# FPGA.net
KiCad netlist of a schematic drawn in Altium Designer
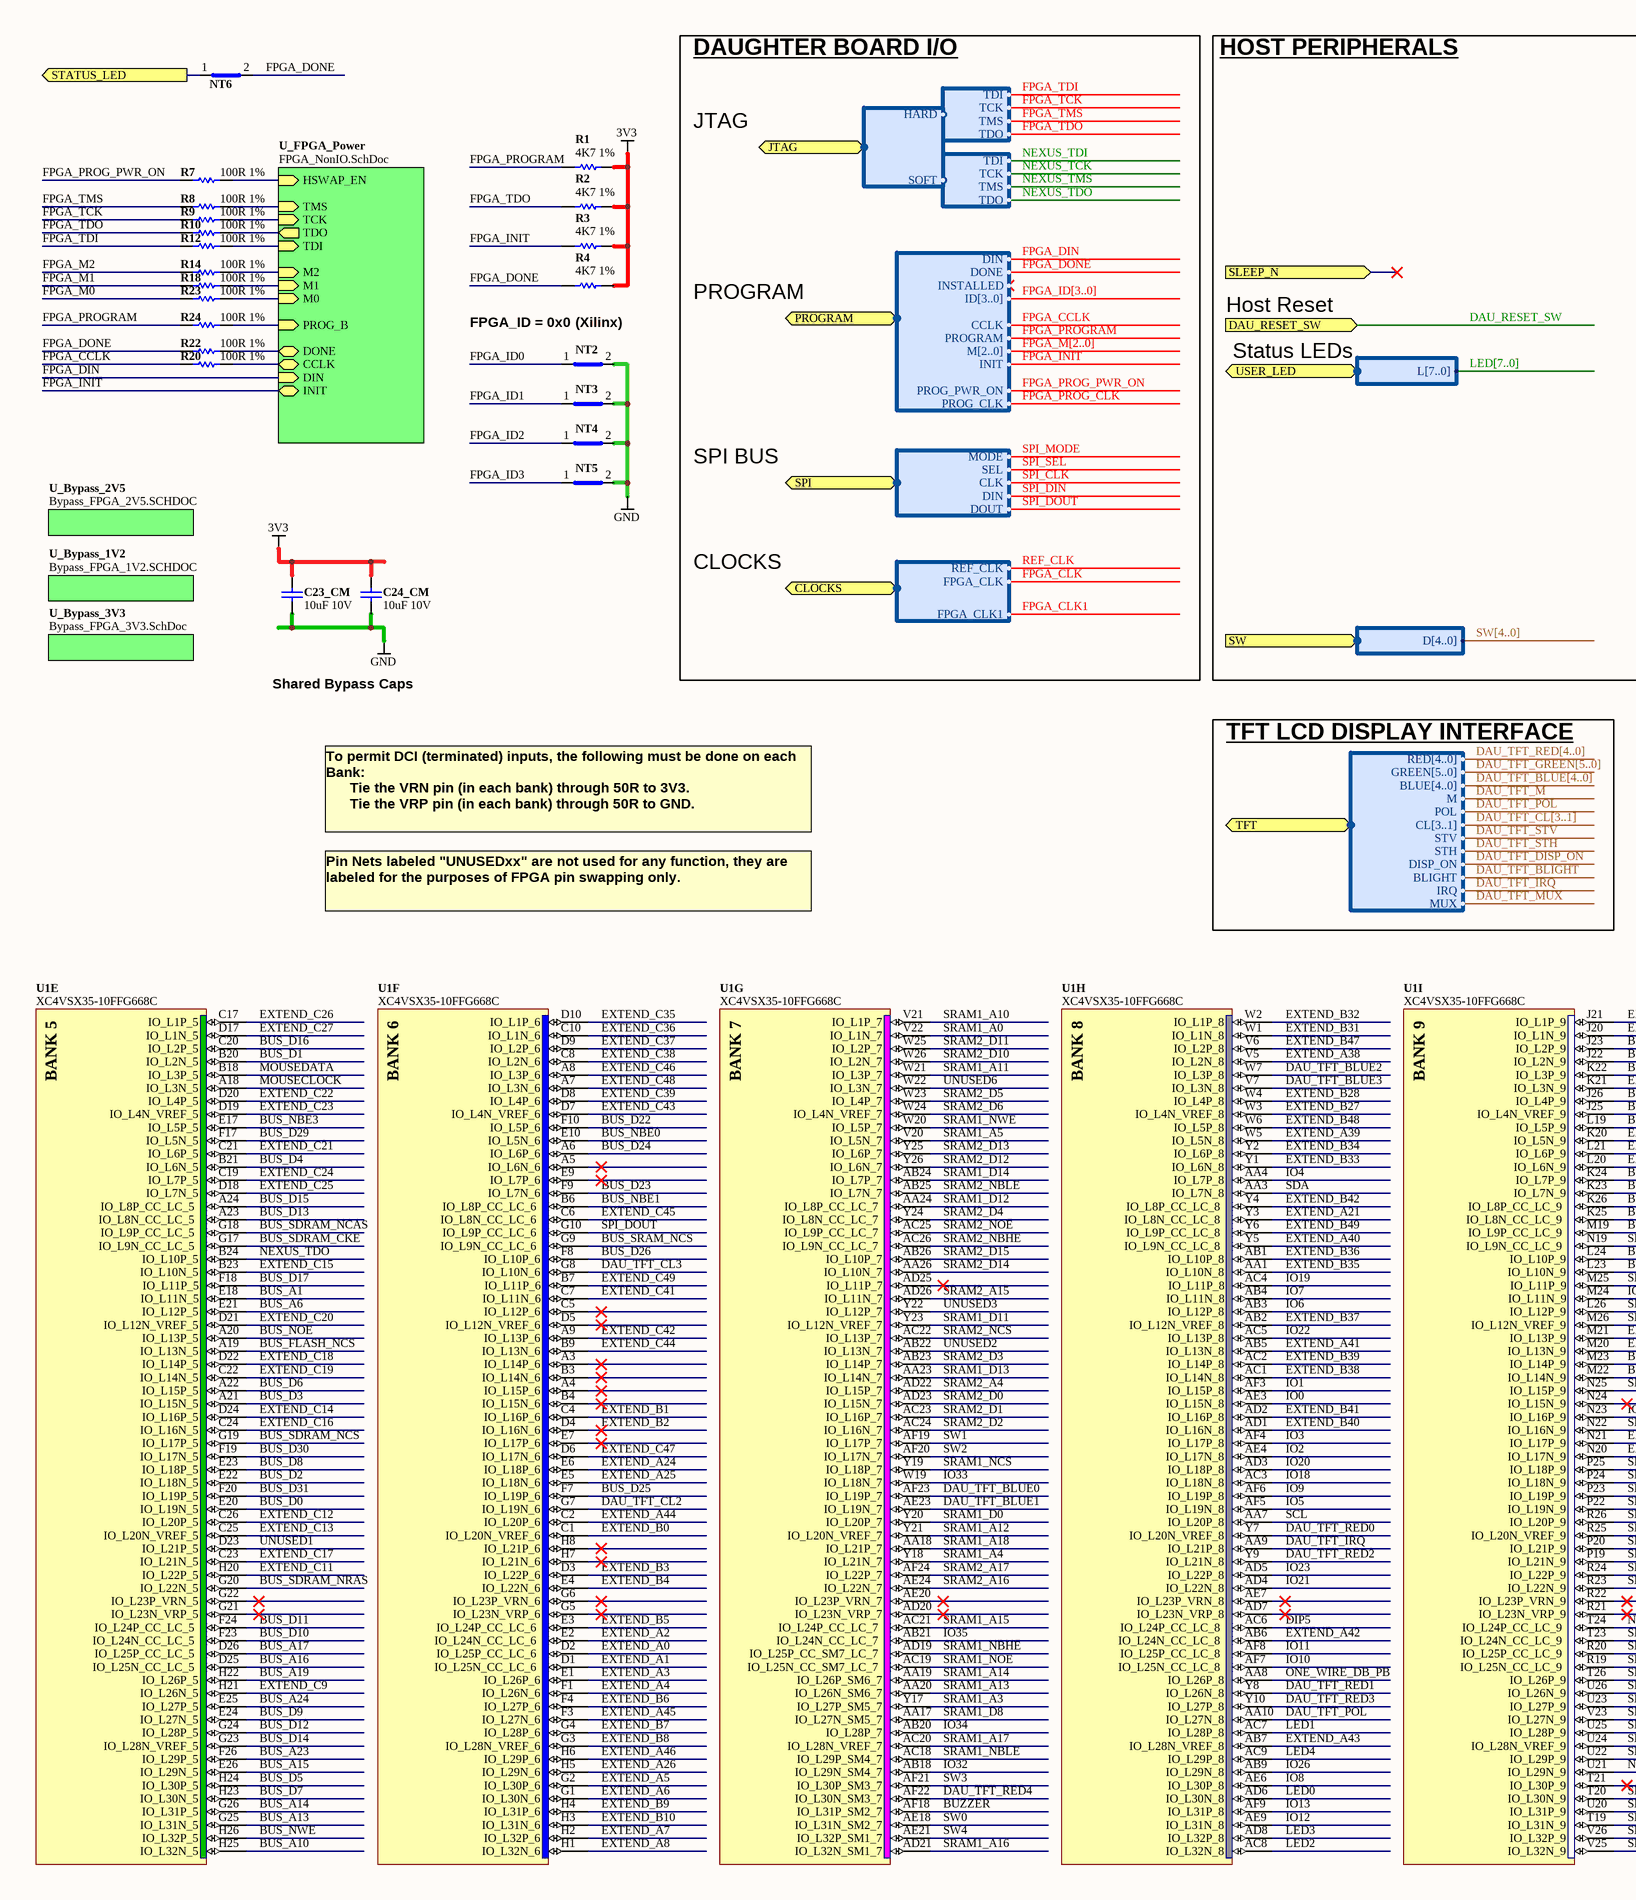
[diagram p0: FPGA.SCHDOC, left]
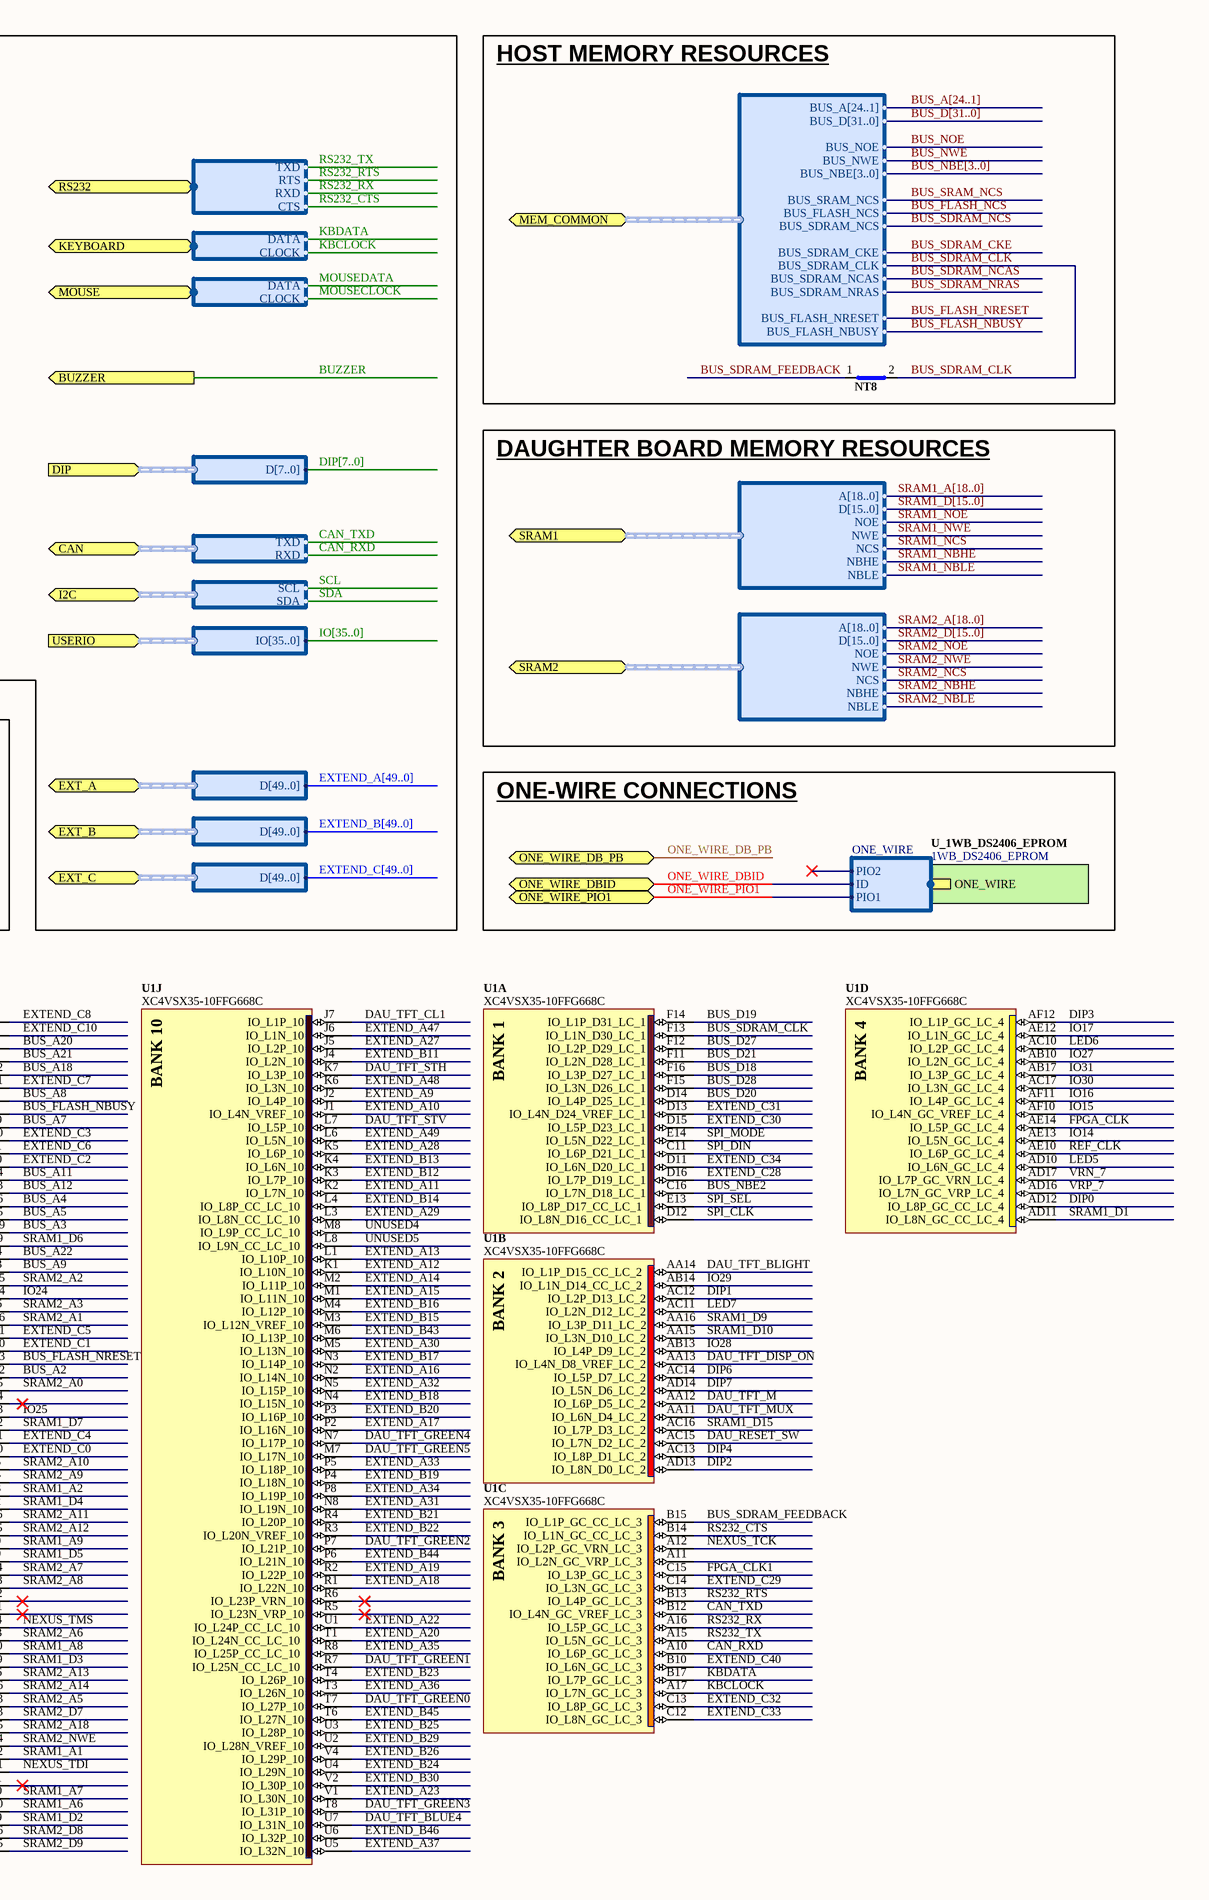
[diagram p1: FPGA.SCHDOC, right]

(export (version "E")
  (design (tool "Eeschema 10.0.6"))
  (components
    (comp (ref "C23_CM")
      (value "10uF 10V")
      (footprint "CAPC2012-STAR")
      (description "Capacitor, Ceramic, 10uF 10% 10V 0805 (2012) X5R")
      (fields (field (name "TOLERANCE") "10 %"))
      (libsource (lib "AltiumDesignLibrary") (part "CAP-NP"))
    )
    (comp (ref "C24_CM")
      (value "10uF 10V")
      (footprint "CAPC2012-STAR")
      (description "Capacitor, Ceramic, 10uF 10% 10V 0805 (2012) X5R")
      (fields (field (name "TOLERANCE") "10 %"))
      (libsource (lib "AltiumDesignLibrary") (part "CAP-NP"))
    )
    (comp (ref "NT2")
      (value "Net Tie SMT2")
      (footprint "NETTIE-SMT2-8X8")
      (description "Net-Tie, Surface Mount, 2 x 0.4mm x 0.2mm SMT Pads - For 0.2mm Track")
      (libsource (lib "AltiumDesignLibrary") (part "NETTIE-SMT2"))
    )
    (comp (ref "NT3")
      (value "Net Tie SMT2")
      (footprint "NETTIE-SMT2-8X8")
      (description "Net-Tie, Surface Mount, 2 x 0.4mm x 0.2mm SMT Pads - For 0.2mm Track")
      (libsource (lib "AltiumDesignLibrary") (part "NETTIE-SMT2"))
    )
    (comp (ref "NT4")
      (value "Net Tie SMT2")
      (footprint "NETTIE-SMT2-8X8")
      (description "Net-Tie, Surface Mount, 2 x 0.4mm x 0.2mm SMT Pads - For 0.2mm Track")
      (libsource (lib "AltiumDesignLibrary") (part "NETTIE-SMT2"))
    )
    (comp (ref "NT5")
      (value "Net Tie SMT2")
      (footprint "NETTIE-SMT2-8X8")
      (description "Net-Tie, Surface Mount, 2 x 0.4mm x 0.2mm SMT Pads - For 0.2mm Track")
      (libsource (lib "AltiumDesignLibrary") (part "NETTIE-SMT2"))
    )
    (comp (ref "NT6")
      (value "Net Tie SMT2")
      (footprint "NETTIE-SMT2-8X8")
      (description "Net-Tie, Surface Mount, 2 x 0.4mm x 0.2mm SMT Pads - For 0.2mm Track")
      (libsource (lib "AltiumDesignLibrary") (part "NETTIE-SMT2"))
    )
    (comp (ref "NT8")
      (value "Net Tie SMT2")
      (footprint "NETTIE-SMT2-8X8")
      (description "Net-Tie, Surface Mount, 2 x 0.4mm x 0.2mm SMT Pads - For 0.2mm Track")
      (libsource (lib "AltiumDesignLibrary") (part "NETTIE-SMT2"))
    )
    (comp (ref "R1")
      (value "4K7 1%")
      (footprint "RESC1005-STAR")
      (description "Resistor, 4K7 1% 0402 (1005)")
      (fields (field (name "TOLERANCE") "1 %"))
      (libsource (lib "AltiumDesignLibrary") (part "RES"))
    )
    (comp (ref "R2")
      (value "4K7 1%")
      (footprint "RESC1005-STAR")
      (description "Resistor, 4K7 1% 0402 (1005)")
      (fields (field (name "TOLERANCE") "1 %"))
      (libsource (lib "AltiumDesignLibrary") (part "RES"))
    )
    (comp (ref "R3")
      (value "4K7 1%")
      (footprint "RESC1005-STAR")
      (description "Resistor, 4K7 1% 0402 (1005)")
      (fields (field (name "TOLERANCE") "1 %"))
      (libsource (lib "AltiumDesignLibrary") (part "RES"))
    )
    (comp (ref "R4")
      (value "4K7 1%")
      (footprint "RESC1005-STAR")
      (description "Resistor, 4K7 1% 0402 (1005)")
      (fields (field (name "TOLERANCE") "1 %"))
      (libsource (lib "AltiumDesignLibrary") (part "RES"))
    )
    (comp (ref "R7")
      (value "100R 1%")
      (footprint "RESC1005-STAR")
      (description "Resistor, 100R 1% 0402 (1005)")
      (fields (field (name "TOLERANCE") "1 %"))
      (libsource (lib "AltiumDesignLibrary") (part "RES"))
    )
    (comp (ref "R8")
      (value "100R 1%")
      (footprint "RESC1005-STAR")
      (description "Resistor, 100R 1% 0402 (1005)")
      (fields (field (name "TOLERANCE") "1 %"))
      (libsource (lib "AltiumDesignLibrary") (part "RES"))
    )
    (comp (ref "R9")
      (value "100R 1%")
      (footprint "RESC1005-STAR")
      (description "Resistor, 100R 1% 0402 (1005)")
      (fields (field (name "TOLERANCE") "1 %"))
      (libsource (lib "AltiumDesignLibrary") (part "RES"))
    )
    (comp (ref "R10")
      (value "100R 1%")
      (footprint "RESC1005-STAR")
      (description "Resistor, 100R 1% 0402 (1005)")
      (fields (field (name "TOLERANCE") "1 %"))
      (libsource (lib "AltiumDesignLibrary") (part "RES"))
    )
    (comp (ref "R12")
      (value "100R 1%")
      (footprint "RESC1005-STAR")
      (description "Resistor, 100R 1% 0402 (1005)")
      (fields (field (name "TOLERANCE") "1 %"))
      (libsource (lib "AltiumDesignLibrary") (part "RES"))
    )
    (comp (ref "R14")
      (value "100R 1%")
      (footprint "RESC1005-STAR")
      (description "Resistor, 100R 1% 0402 (1005)")
      (fields (field (name "TOLERANCE") "1 %"))
      (libsource (lib "AltiumDesignLibrary") (part "RES"))
    )
    (comp (ref "R18")
      (value "100R 1%")
      (footprint "RESC1005-STAR")
      (description "Resistor, 100R 1% 0402 (1005)")
      (fields (field (name "TOLERANCE") "1 %"))
      (libsource (lib "AltiumDesignLibrary") (part "RES"))
    )
    (comp (ref "R20")
      (value "100R 1%")
      (footprint "RESC1005-STAR")
      (description "Resistor, 100R 1% 0402 (1005)")
      (fields (field (name "TOLERANCE") "1 %"))
      (libsource (lib "AltiumDesignLibrary") (part "RES"))
    )
    (comp (ref "R22")
      (value "100R 1%")
      (footprint "RESC1005-STAR")
      (description "Resistor, 100R 1% 0402 (1005)")
      (fields (field (name "TOLERANCE") "1 %"))
      (libsource (lib "AltiumDesignLibrary") (part "RES"))
    )
    (comp (ref "R23")
      (value "100R 1%")
      (footprint "RESC1005-STAR")
      (description "Resistor, 100R 1% 0402 (1005)")
      (fields (field (name "TOLERANCE") "1 %"))
      (libsource (lib "AltiumDesignLibrary") (part "RES"))
    )
    (comp (ref "R24")
      (value "100R 1%")
      (footprint "RESC1005-STAR")
      (description "Resistor, 100R 1% 0402 (1005)")
      (fields (field (name "TOLERANCE") "1 %"))
      (libsource (lib "AltiumDesignLibrary") (part "RES"))
    )
    (comp (ref "U1")
      (value "XC4VSX35-10FFG668C")
      (footprint "XC4VLX25-10FF668C")
      (description "FPGA, Xilinx Virtex-4, XC4VSX35")
      (libsource (lib "AltiumDesignLibrary") (part "XC4VSX35-10FFG668C"))
    )
  )
  (nets
    (net (code "20") (name "/BUS_A1") (class "Default")
      (node (ref "U1") (pin "E18") (pinfunction "IO_L11N_5_E18") (pintype "bidirectional"))
    )
    (net (code "21") (name "/BUS_A2") (class "Default")
      (node (ref "U1") (pin "M22") (pinfunction "IO_L14N_9_M22") (pintype "bidirectional"))
    )
    (net (code "22") (name "/BUS_A3") (class "Default")
      (node (ref "U1") (pin "M19") (pinfunction "IO_L9P_CC_LC_9_M19") (pintype "bidirectional"))
    )
    (net (code "23") (name "/BUS_A4") (class "Default")
      (node (ref "U1") (pin "K26") (pinfunction "IO_L8P_CC_LC_9_K26") (pintype "bidirectional"))
    )
    (net (code "24") (name "/BUS_A5") (class "Default")
      (node (ref "U1") (pin "K25") (pinfunction "IO_L8N_CC_LC_9_K25") (pintype "bidirectional"))
    )
    (net (code "25") (name "/BUS_A6") (class "Default")
      (node (ref "U1") (pin "E21") (pinfunction "IO_L12P_5_E21") (pintype "bidirectional"))
    )
    (net (code "26") (name "/BUS_A7") (class "Default")
      (node (ref "U1") (pin "L19") (pinfunction "IO_L5P_9_L19") (pintype "bidirectional"))
    )
    (net (code "27") (name "/BUS_A8") (class "Default")
      (node (ref "U1") (pin "J26") (pinfunction "IO_L4P_9_J26") (pintype "bidirectional"))
    )
    (net (code "28") (name "/BUS_A9") (class "Default")
      (node (ref "U1") (pin "L23") (pinfunction "IO_L10N_9_L23") (pintype "bidirectional"))
    )
    (net (code "29") (name "/BUS_A10") (class "Default")
      (node (ref "U1") (pin "H25") (pinfunction "IO_L32N_5_H25") (pintype "bidirectional"))
    )
    (net (code "30") (name "/BUS_A11") (class "Default")
      (node (ref "U1") (pin "K24") (pinfunction "IO_L7P_9_K24") (pintype "bidirectional"))
    )
    (net (code "31") (name "/BUS_A12") (class "Default")
      (node (ref "U1") (pin "K23") (pinfunction "IO_L7N_9_K23") (pintype "bidirectional"))
    )
    (net (code "32") (name "/BUS_A13") (class "Default")
      (node (ref "U1") (pin "G25") (pinfunction "IO_L31N_5_G25") (pintype "bidirectional"))
    )
    (net (code "33") (name "/BUS_A14") (class "Default")
      (node (ref "U1") (pin "G26") (pinfunction "IO_L31P_5_G26") (pintype "bidirectional"))
    )
    (net (code "34") (name "/BUS_A15") (class "Default")
      (node (ref "U1") (pin "E26") (pinfunction "IO_L29N_5_E26") (pintype "bidirectional"))
    )
    (net (code "35") (name "/BUS_A16") (class "Default")
      (node (ref "U1") (pin "D25") (pinfunction "IO_L25N_CC_LC_5_D25") (pintype "bidirectional"))
    )
    (net (code "36") (name "/BUS_A17") (class "Default")
      (node (ref "U1") (pin "D26") (pinfunction "IO_L25P_CC_LC_5_D26") (pintype "bidirectional"))
    )
    (net (code "37") (name "/BUS_A18") (class "Default")
      (node (ref "U1") (pin "K22") (pinfunction "IO_L3P_9_K22") (pintype "bidirectional"))
    )
    (net (code "38") (name "/BUS_A19") (class "Default")
      (node (ref "U1") (pin "H22") (pinfunction "IO_L26P_5_H22") (pintype "bidirectional"))
    )
    (net (code "39") (name "/BUS_A20") (class "Default")
      (node (ref "U1") (pin "J23") (pinfunction "IO_L2P_9_J23") (pintype "bidirectional"))
    )
    (net (code "40") (name "/BUS_A21") (class "Default")
      (node (ref "U1") (pin "J22") (pinfunction "IO_L2N_9_J22") (pintype "bidirectional"))
    )
    (net (code "41") (name "/BUS_A22") (class "Default")
      (node (ref "U1") (pin "L24") (pinfunction "IO_L10P_9_L24") (pintype "bidirectional"))
    )
    (net (code "42") (name "/BUS_A23") (class "Default")
      (node (ref "U1") (pin "F26") (pinfunction "IO_L29P_5_F26") (pintype "bidirectional"))
    )
    (net (code "43") (name "/BUS_A24") (class "Default")
      (node (ref "U1") (pin "E25") (pinfunction "IO_L27P_5_E25") (pintype "bidirectional"))
    )
    (net (code "44") (name "/BUS_D0") (class "Default")
      (node (ref "U1") (pin "E20") (pinfunction "IO_L19N_5_E20") (pintype "bidirectional"))
    )
    (net (code "45") (name "/BUS_D1") (class "Default")
      (node (ref "U1") (pin "B20") (pinfunction "IO_L2N_5_B20") (pintype "bidirectional"))
    )
    (net (code "46") (name "/BUS_D2") (class "Default")
      (node (ref "U1") (pin "E22") (pinfunction "IO_L18N_5_E22") (pintype "bidirectional"))
    )
    (net (code "47") (name "/BUS_D3") (class "Default")
      (node (ref "U1") (pin "A21") (pinfunction "IO_L15N_5_A21") (pintype "bidirectional"))
    )
    (net (code "48") (name "/BUS_D4") (class "Default")
      (node (ref "U1") (pin "B21") (pinfunction "IO_L6N_5_B21") (pintype "bidirectional"))
    )
    (net (code "49") (name "/BUS_D5") (class "Default")
      (node (ref "U1") (pin "H24") (pinfunction "IO_L30P_5_H24") (pintype "bidirectional"))
    )
    (net (code "50") (name "/BUS_D6") (class "Default")
      (node (ref "U1") (pin "A22") (pinfunction "IO_L15P_5_A22") (pintype "bidirectional"))
    )
    (net (code "51") (name "/BUS_D7") (class "Default")
      (node (ref "U1") (pin "H23") (pinfunction "IO_L30N_5_H23") (pintype "bidirectional"))
    )
    (net (code "52") (name "/BUS_D8") (class "Default")
      (node (ref "U1") (pin "E23") (pinfunction "IO_L18P_5_E23") (pintype "bidirectional"))
    )
    (net (code "53") (name "/BUS_D9") (class "Default")
      (node (ref "U1") (pin "E24") (pinfunction "IO_L27N_5_E24") (pintype "bidirectional"))
    )
    (net (code "54") (name "/BUS_D10") (class "Default")
      (node (ref "U1") (pin "F23") (pinfunction "IO_L24N_CC_LC_5_F23") (pintype "bidirectional"))
    )
    (net (code "55") (name "/BUS_D11") (class "Default")
      (node (ref "U1") (pin "F24") (pinfunction "IO_L24P_CC_LC_5_F24") (pintype "bidirectional"))
    )
    (net (code "56") (name "/BUS_D12") (class "Default")
      (node (ref "U1") (pin "G24") (pinfunction "IO_L28P_5_G24") (pintype "bidirectional"))
    )
    (net (code "57") (name "/BUS_D13") (class "Default")
      (node (ref "U1") (pin "A23") (pinfunction "IO_L8N_CC_LC_5_A23") (pintype "bidirectional"))
    )
    (net (code "58") (name "/BUS_D14") (class "Default")
      (node (ref "U1") (pin "G23") (pinfunction "IO_L28N_VREF_5_G23") (pintype "bidirectional"))
    )
    (net (code "59") (name "/BUS_D15") (class "Default")
      (node (ref "U1") (pin "A24") (pinfunction "IO_L8P_CC_LC_5_A24") (pintype "bidirectional"))
    )
    (net (code "60") (name "/BUS_D16") (class "Default")
      (node (ref "U1") (pin "C20") (pinfunction "IO_L2P_5_C20") (pintype "bidirectional"))
    )
    (net (code "61") (name "/BUS_D17") (class "Default")
      (node (ref "U1") (pin "F18") (pinfunction "IO_L11P_5_F18") (pintype "bidirectional"))
    )
    (net (code "62") (name "/BUS_D18") (class "Default")
      (node (ref "U1") (pin "F16") (pinfunction "IO_L3P_D27_LC_1_F16") (pintype "bidirectional"))
    )
    (net (code "63") (name "/BUS_D19") (class "Default")
      (node (ref "U1") (pin "F14") (pinfunction "IO_L1P_D31_LC_1_F14") (pintype "bidirectional"))
    )
    (net (code "64") (name "/BUS_D20") (class "Default")
      (node (ref "U1") (pin "D14") (pinfunction "IO_L4P_D25_LC_1_D14") (pintype "bidirectional"))
    )
    (net (code "65") (name "/BUS_D21") (class "Default")
      (node (ref "U1") (pin "F11") (pinfunction "IO_L2N_D28_LC_1_F11") (pintype "bidirectional"))
    )
    (net (code "66") (name "/BUS_D22") (class "Default")
      (node (ref "U1") (pin "F10") (pinfunction "IO_L5P_6_F10") (pintype "bidirectional"))
    )
    (net (code "67") (name "/BUS_D23") (class "Default")
      (node (ref "U1") (pin "F9") (pinfunction "IO_L7N_6_F9") (pintype "bidirectional"))
    )
    (net (code "68") (name "/BUS_D24") (class "Default")
      (node (ref "U1") (pin "A6") (pinfunction "IO_L6P_6_A6") (pintype "bidirectional"))
    )
    (net (code "69") (name "/BUS_D25") (class "Default")
      (node (ref "U1") (pin "F7") (pinfunction "IO_L19P_6_F7") (pintype "bidirectional"))
    )
    (net (code "70") (name "/BUS_D26") (class "Default")
      (node (ref "U1") (pin "F8") (pinfunction "IO_L10P_6_F8") (pintype "bidirectional"))
    )
    (net (code "71") (name "/BUS_D27") (class "Default")
      (node (ref "U1") (pin "F12") (pinfunction "IO_L2P_D29_LC_1_F12") (pintype "bidirectional"))
    )
    (net (code "72") (name "/BUS_D28") (class "Default")
      (node (ref "U1") (pin "F15") (pinfunction "IO_L3N_D26_LC_1_F15") (pintype "bidirectional"))
    )
    (net (code "73") (name "/BUS_D29") (class "Default")
      (node (ref "U1") (pin "F17") (pinfunction "IO_L5N_5_F17") (pintype "bidirectional"))
    )
    (net (code "74") (name "/BUS_D30") (class "Default")
      (node (ref "U1") (pin "F19") (pinfunction "IO_L17N_5_F19") (pintype "bidirectional"))
    )
    (net (code "75") (name "/BUS_D31") (class "Default")
      (node (ref "U1") (pin "F20") (pinfunction "IO_L19P_5_F20") (pintype "bidirectional"))
    )
    (net (code "77") (name "/BUS_FLASH_NBUSY") (class "Default")
      (node (ref "U1") (pin "J25") (pinfunction "IO_L4N_VREF_9_J25") (pintype "bidirectional"))
    )
    (net (code "78") (name "/BUS_FLASH_NCS") (class "Default")
      (node (ref "U1") (pin "A19") (pinfunction "IO_L13N_5_A19") (pintype "bidirectional"))
    )
    (net (code "79") (name "/BUS_FLASH_NRESET") (class "Default")
      (node (ref "U1") (pin "M23") (pinfunction "IO_L14P_9_M23") (pintype "bidirectional"))
    )
    (net (code "80") (name "/BUS_NBE0") (class "Default")
      (node (ref "U1") (pin "E10") (pinfunction "IO_L5N_6_E10") (pintype "bidirectional"))
    )
    (net (code "81") (name "/BUS_NBE1") (class "Default")
      (node (ref "U1") (pin "B6") (pinfunction "IO_L8P_CC_LC_6_B6") (pintype "bidirectional"))
    )
    (net (code "82") (name "/BUS_NBE2") (class "Default")
      (node (ref "U1") (pin "C16") (pinfunction "IO_L7N_D18_LC_1_C16") (pintype "bidirectional"))
    )
    (net (code "83") (name "/BUS_NBE3") (class "Default")
      (node (ref "U1") (pin "E17") (pinfunction "IO_L5P_5_E17") (pintype "bidirectional"))
    )
    (net (code "85") (name "/BUS_NOE") (class "Default")
      (node (ref "U1") (pin "A20") (pinfunction "IO_L13P_5_A20") (pintype "bidirectional"))
    )
    (net (code "86") (name "/BUS_NWE") (class "Default")
      (node (ref "U1") (pin "H26") (pinfunction "IO_L32P_5_H26") (pintype "bidirectional"))
    )
    (net (code "87") (name "/BUS_SDRAM_CKE") (class "Default")
      (node (ref "U1") (pin "G17") (pinfunction "IO_L9N_CC_LC_5_G17") (pintype "bidirectional"))
    )
    (net (code "88") (name "/BUS_SDRAM_CLK") (class "Default")
      (node (ref "NT8") (pin "2") (pinfunction "Net2_2") (pintype "passive"))
      (node (ref "U1") (pin "F13") (pinfunction "IO_L1N_D30_LC_1_F13") (pintype "bidirectional"))
    )
    (net (code "89") (name "/BUS_SDRAM_FEEDBACK") (class "Default")
      (node (ref "NT8") (pin "1") (pinfunction "Net1_1") (pintype "passive"))
      (node (ref "U1") (pin "B15") (pinfunction "IO_L1P_GC_CC_LC_3_B15") (pintype "bidirectional"))
    )
    (net (code "90") (name "/BUS_SDRAM_NCAS") (class "Default")
      (node (ref "U1") (pin "G18") (pinfunction "IO_L9P_CC_LC_5_G18") (pintype "bidirectional"))
    )
    (net (code "91") (name "/BUS_SDRAM_NCS") (class "Default")
      (node (ref "U1") (pin "G19") (pinfunction "IO_L17P_5_G19") (pintype "bidirectional"))
    )
    (net (code "92") (name "/BUS_SDRAM_NRAS") (class "Default")
      (node (ref "U1") (pin "G20") (pinfunction "IO_L22N_5_G20") (pintype "bidirectional"))
    )
    (net (code "93") (name "/BUS_SRAM_NCS") (class "Default")
      (node (ref "U1") (pin "G9") (pinfunction "IO_L9N_CC_LC_6_G9") (pintype "bidirectional"))
    )
    (net (code "94") (name "/BUZZER") (class "Default")
      (node (ref "U1") (pin "AF18") (pinfunction "IO_L31P_SM2_7_AF18") (pintype "bidirectional"))
    )
    (net (code "95") (name "/CAN_RXD") (class "Default")
      (node (ref "U1") (pin "A10") (pinfunction "IO_L6P_GC_LC_3_A10") (pintype "bidirectional"))
    )
    (net (code "96") (name "/CAN_TXD") (class "Default")
      (node (ref "U1") (pin "B12") (pinfunction "IO_L4N_GC_VREF_LC_3_B12") (pintype "bidirectional"))
    )
    (net (code "97") (name "/CCLK") (class "Default")
      (node (ref "R20") (pin "2") (pinfunction "2_2") (pintype "passive"))
    )
    (net (code "98") (name "/DAU_RESET_SW") (class "Default")
      (node (ref "U1") (pin "AC15") (pinfunction "IO_L7N_D2_LC_2_AC15") (pintype "bidirectional"))
    )
    (net (code "99") (name "/DAU_TFT_BLIGHT") (class "Default")
      (node (ref "U1") (pin "AA14") (pinfunction "IO_L1P_D15_CC_LC_2_AA14") (pintype "bidirectional"))
    )
    (net (code "100") (name "/DAU_TFT_BLUE0") (class "Default")
      (node (ref "U1") (pin "AF23") (pinfunction "IO_L19P_7_AF23") (pintype "bidirectional"))
    )
    (net (code "101") (name "/DAU_TFT_BLUE1") (class "Default")
      (node (ref "U1") (pin "AE23") (pinfunction "IO_L19N_7_AE23") (pintype "bidirectional"))
    )
    (net (code "102") (name "/DAU_TFT_BLUE2") (class "Default")
      (node (ref "U1") (pin "W7") (pinfunction "IO_L3P_8_W7") (pintype "bidirectional"))
    )
    (net (code "103") (name "/DAU_TFT_BLUE3") (class "Default")
      (node (ref "U1") (pin "V7") (pinfunction "IO_L3N_8_V7") (pintype "bidirectional"))
    )
    (net (code "104") (name "/DAU_TFT_BLUE4") (class "Default")
      (node (ref "U1") (pin "U7") (pinfunction "IO_L31N_10_U7") (pintype "bidirectional"))
    )
    (net (code "106") (name "/DAU_TFT_CL1") (class "Default")
      (node (ref "U1") (pin "J7") (pinfunction "IO_L1P_10_J7") (pintype "bidirectional"))
    )
    (net (code "107") (name "/DAU_TFT_CL2") (class "Default")
      (node (ref "U1") (pin "G7") (pinfunction "IO_L19N_6_G7") (pintype "bidirectional"))
    )
    (net (code "108") (name "/DAU_TFT_CL3") (class "Default")
      (node (ref "U1") (pin "G8") (pinfunction "IO_L10N_6_G8") (pintype "bidirectional"))
    )
    (net (code "110") (name "/DAU_TFT_DISP_ON") (class "Default")
      (node (ref "U1") (pin "AA13") (pinfunction "IO_L4N_D8_VREF_LC_2_AA13") (pintype "bidirectional"))
    )
    (net (code "111") (name "/DAU_TFT_GREEN0") (class "Default")
      (node (ref "U1") (pin "T7") (pinfunction "IO_L27P_10_T7") (pintype "bidirectional"))
    )
    (net (code "112") (name "/DAU_TFT_GREEN1") (class "Default")
      (node (ref "U1") (pin "R7") (pinfunction "IO_L25N_CC_LC_10_R7") (pintype "bidirectional"))
    )
    (net (code "113") (name "/DAU_TFT_GREEN2") (class "Default")
      (node (ref "U1") (pin "P7") (pinfunction "IO_L21P_10_P7") (pintype "bidirectional"))
    )
    (net (code "114") (name "/DAU_TFT_GREEN3") (class "Default")
      (node (ref "U1") (pin "T8") (pinfunction "IO_L31P_10_T8") (pintype "bidirectional"))
    )
    (net (code "115") (name "/DAU_TFT_GREEN4") (class "Default")
      (node (ref "U1") (pin "N7") (pinfunction "IO_L17P_10_N7") (pintype "bidirectional"))
    )
    (net (code "116") (name "/DAU_TFT_GREEN5") (class "Default")
      (node (ref "U1") (pin "M7") (pinfunction "IO_L17N_10_M7") (pintype "bidirectional"))
    )
    (net (code "117") (name "/DAU_TFT_IRQ") (class "Default")
      (node (ref "U1") (pin "AA9") (pinfunction "IO_L21P_8_AA9") (pintype "bidirectional"))
    )
    (net (code "118") (name "/DAU_TFT_M") (class "Default")
      (node (ref "U1") (pin "AA12") (pinfunction "IO_L6P_D5_LC_2_AA12") (pintype "bidirectional"))
    )
    (net (code "119") (name "/DAU_TFT_MUX") (class "Default")
      (node (ref "U1") (pin "AA11") (pinfunction "IO_L6N_D4_LC_2_AA11") (pintype "bidirectional"))
    )
    (net (code "120") (name "/DAU_TFT_POL") (class "Default")
      (node (ref "U1") (pin "AA10") (pinfunction "IO_L27N_8_AA10") (pintype "bidirectional"))
    )
    (net (code "121") (name "/DAU_TFT_RED0") (class "Default")
      (node (ref "U1") (pin "Y7") (pinfunction "IO_L20N_VREF_8_Y7") (pintype "bidirectional"))
    )
    (net (code "122") (name "/DAU_TFT_RED1") (class "Default")
      (node (ref "U1") (pin "Y8") (pinfunction "IO_L26N_8_Y8") (pintype "bidirectional"))
    )
    (net (code "123") (name "/DAU_TFT_RED2") (class "Default")
      (node (ref "U1") (pin "Y9") (pinfunction "IO_L21N_8_Y9") (pintype "bidirectional"))
    )
    (net (code "124") (name "/DAU_TFT_RED3") (class "Default")
      (node (ref "U1") (pin "Y10") (pinfunction "IO_L27P_8_Y10") (pintype "bidirectional"))
    )
    (net (code "125") (name "/DAU_TFT_RED4") (class "Default")
      (node (ref "U1") (pin "AF22") (pinfunction "IO_L30N_SM3_7_AF22") (pintype "bidirectional"))
    )
    (net (code "127") (name "/DAU_TFT_STH") (class "Default")
      (node (ref "U1") (pin "K7") (pinfunction "IO_L3P_10_K7") (pintype "bidirectional"))
    )
    (net (code "128") (name "/DAU_TFT_STV") (class "Default")
      (node (ref "U1") (pin "L7") (pinfunction "IO_L5P_10_L7") (pintype "bidirectional"))
    )
    (net (code "129") (name "/DIP0") (class "Default")
      (node (ref "U1") (pin "AD12") (pinfunction "IO_L8P_GC_CC_LC_4_AD12") (pintype "bidirectional"))
    )
    (net (code "130") (name "/DIP1") (class "Default")
      (node (ref "U1") (pin "AC12") (pinfunction "IO_L2P_D13_LC_2_AC12") (pintype "bidirectional"))
    )
    (net (code "131") (name "/DIP2") (class "Default")
      (node (ref "U1") (pin "AD13") (pinfunction "IO_L8N_D0_LC_2_AD13") (pintype "bidirectional"))
    )
    (net (code "132") (name "/DIP3") (class "Default")
      (node (ref "U1") (pin "AF12") (pinfunction "IO_L1P_GC_LC_4_AF12") (pintype "bidirectional"))
    )
    (net (code "133") (name "/DIP4") (class "Default")
      (node (ref "U1") (pin "AC13") (pinfunction "IO_L8P_D1_LC_2_AC13") (pintype "bidirectional"))
    )
    (net (code "134") (name "/DIP5") (class "Default")
      (node (ref "U1") (pin "AC6") (pinfunction "IO_L24P_CC_LC_8_AC6") (pintype "bidirectional"))
    )
    (net (code "135") (name "/DIP6") (class "Default")
      (node (ref "U1") (pin "AC14") (pinfunction "IO_L5P_D7_LC_2_AC14") (pintype "bidirectional"))
    )
    (net (code "136") (name "/DIP7") (class "Default")
      (node (ref "U1") (pin "AD14") (pinfunction "IO_L5N_D6_LC_2_AD14") (pintype "bidirectional"))
    )
    (net (code "138") (name "/DONE") (class "Default")
      (node (ref "R22") (pin "2") (pinfunction "2_2") (pintype "passive"))
    )
    (net (code "139") (name "/EXTEND_A0") (class "Default")
      (node (ref "U1") (pin "D2") (pinfunction "IO_L25P_CC_LC_6_D2") (pintype "bidirectional"))
    )
    (net (code "140") (name "/EXTEND_A1") (class "Default")
      (node (ref "U1") (pin "D1") (pinfunction "IO_L25N_CC_LC_6_D1") (pintype "bidirectional"))
    )
    (net (code "141") (name "/EXTEND_A2") (class "Default")
      (node (ref "U1") (pin "E2") (pinfunction "IO_L24N_CC_LC_6_E2") (pintype "bidirectional"))
    )
    (net (code "142") (name "/EXTEND_A3") (class "Default")
      (node (ref "U1") (pin "E1") (pinfunction "IO_L26P_6_E1") (pintype "bidirectional"))
    )
    (net (code "143") (name "/EXTEND_A4") (class "Default")
      (node (ref "U1") (pin "F1") (pinfunction "IO_L26N_6_F1") (pintype "bidirectional"))
    )
    (net (code "144") (name "/EXTEND_A5") (class "Default")
      (node (ref "U1") (pin "G2") (pinfunction "IO_L30P_6_G2") (pintype "bidirectional"))
    )
    (net (code "145") (name "/EXTEND_A6") (class "Default")
      (node (ref "U1") (pin "G1") (pinfunction "IO_L30N_6_G1") (pintype "bidirectional"))
    )
    (net (code "146") (name "/EXTEND_A7") (class "Default")
      (node (ref "U1") (pin "H2") (pinfunction "IO_L32P_6_H2") (pintype "bidirectional"))
    )
    (net (code "147") (name "/EXTEND_A8") (class "Default")
      (node (ref "U1") (pin "H1") (pinfunction "IO_L32N_6_H1") (pintype "bidirectional"))
    )
    (net (code "148") (name "/EXTEND_A9") (class "Default")
      (node (ref "U1") (pin "J2") (pinfunction "IO_L4P_10_J2") (pintype "bidirectional"))
    )
    (net (code "149") (name "/EXTEND_A10") (class "Default")
      (node (ref "U1") (pin "J1") (pinfunction "IO_L4N_VREF_10_J1") (pintype "bidirectional"))
    )
    (net (code "150") (name "/EXTEND_A11") (class "Default")
      (node (ref "U1") (pin "K2") (pinfunction "IO_L7N_10_K2") (pintype "bidirectional"))
    )
    (net (code "151") (name "/EXTEND_A12") (class "Default")
      (node (ref "U1") (pin "K1") (pinfunction "IO_L10N_10_K1") (pintype "bidirectional"))
    )
    (net (code "152") (name "/EXTEND_A13") (class "Default")
      (node (ref "U1") (pin "L1") (pinfunction "IO_L10P_10_L1") (pintype "bidirectional"))
    )
    (net (code "153") (name "/EXTEND_A14") (class "Default")
      (node (ref "U1") (pin "M2") (pinfunction "IO_L11P_10_M2") (pintype "bidirectional"))
    )
    (net (code "154") (name "/EXTEND_A15") (class "Default")
      (node (ref "U1") (pin "M1") (pinfunction "IO_L11N_10_M1") (pintype "bidirectional"))
    )
    (net (code "155") (name "/EXTEND_A16") (class "Default")
      (node (ref "U1") (pin "N2") (pinfunction "IO_L14N_10_N2") (pintype "bidirectional"))
    )
    (net (code "156") (name "/EXTEND_A17") (class "Default")
      (node (ref "U1") (pin "P2") (pinfunction "IO_L16N_10_P2") (pintype "bidirectional"))
    )
    (net (code "157") (name "/EXTEND_A18") (class "Default")
      (node (ref "U1") (pin "R1") (pinfunction "IO_L22N_10_R1") (pintype "bidirectional"))
    )
    (net (code "158") (name "/EXTEND_A19") (class "Default")
      (node (ref "U1") (pin "R2") (pinfunction "IO_L22P_10_R2") (pintype "bidirectional"))
    )
    (net (code "159") (name "/EXTEND_A20") (class "Default")
      (node (ref "U1") (pin "T1") (pinfunction "IO_L24N_CC_LC_10_T1") (pintype "bidirectional"))
    )
    (net (code "160") (name "/EXTEND_A21") (class "Default")
      (node (ref "U1") (pin "Y3") (pinfunction "IO_L8N_CC_LC_8_Y3") (pintype "bidirectional"))
    )
    (net (code "161") (name "/EXTEND_A22") (class "Default")
      (node (ref "U1") (pin "U1") (pinfunction "IO_L24P_CC_LC_10_U1") (pintype "bidirectional"))
    )
    (net (code "162") (name "/EXTEND_A23") (class "Default")
      (node (ref "U1") (pin "V1") (pinfunction "IO_L30N_10_V1") (pintype "bidirectional"))
    )
    (net (code "163") (name "/EXTEND_A24") (class "Default")
      (node (ref "U1") (pin "E6") (pinfunction "IO_L18P_6_E6") (pintype "bidirectional"))
    )
    (net (code "164") (name "/EXTEND_A25") (class "Default")
      (node (ref "U1") (pin "E5") (pinfunction "IO_L18N_6_E5") (pintype "bidirectional"))
    )
    (net (code "165") (name "/EXTEND_A26") (class "Default")
      (node (ref "U1") (pin "H5") (pinfunction "IO_L29N_6_H5") (pintype "bidirectional"))
    )
    (net (code "166") (name "/EXTEND_A27") (class "Default")
      (node (ref "U1") (pin "J5") (pinfunction "IO_L2P_10_J5") (pintype "bidirectional"))
    )
    (net (code "167") (name "/EXTEND_A28") (class "Default")
      (node (ref "U1") (pin "K5") (pinfunction "IO_L6P_10_K5") (pintype "bidirectional"))
    )
    (net (code "168") (name "/EXTEND_A29") (class "Default")
      (node (ref "U1") (pin "L3") (pinfunction "IO_L8N_CC_LC_10_L3") (pintype "bidirectional"))
    )
    (net (code "169") (name "/EXTEND_A30") (class "Default")
      (node (ref "U1") (pin "M5") (pinfunction "IO_L13N_10_M5") (pintype "bidirectional"))
    )
    (net (code "170") (name "/EXTEND_A31") (class "Default")
      (node (ref "U1") (pin "N8") (pinfunction "IO_L19N_10_N8") (pintype "bidirectional"))
    )
    (net (code "171") (name "/EXTEND_A32") (class "Default")
      (node (ref "U1") (pin "N5") (pinfunction "IO_L15P_10_N5") (pintype "bidirectional"))
    )
    (net (code "172") (name "/EXTEND_A33") (class "Default")
      (node (ref "U1") (pin "P5") (pinfunction "IO_L18P_10_P5") (pintype "bidirectional"))
    )
    (net (code "173") (name "/EXTEND_A34") (class "Default")
      (node (ref "U1") (pin "P8") (pinfunction "IO_L19P_10_P8") (pintype "bidirectional"))
    )
    (net (code "174") (name "/EXTEND_A35") (class "Default")
      (node (ref "U1") (pin "R8") (pinfunction "IO_L25P_CC_LC_10_R8") (pintype "bidirectional"))
    )
    (net (code "175") (name "/EXTEND_A36") (class "Default")
      (node (ref "U1") (pin "T3") (pinfunction "IO_L26N_10_T3") (pintype "bidirectional"))
    )
    (net (code "176") (name "/EXTEND_A37") (class "Default")
      (node (ref "U1") (pin "U5") (pinfunction "IO_L32N_10_U5") (pintype "bidirectional"))
    )
    (net (code "177") (name "/EXTEND_A38") (class "Default")
      (node (ref "U1") (pin "V5") (pinfunction "IO_L2N_8_V5") (pintype "bidirectional"))
    )
    (net (code "178") (name "/EXTEND_A39") (class "Default")
      (node (ref "U1") (pin "W5") (pinfunction "IO_L5N_8_W5") (pintype "bidirectional"))
    )
    (net (code "179") (name "/EXTEND_A40") (class "Default")
      (node (ref "U1") (pin "Y5") (pinfunction "IO_L9N_CC_LC_8_Y5") (pintype "bidirectional"))
    )
    (net (code "180") (name "/EXTEND_A41") (class "Default")
      (node (ref "U1") (pin "AB5") (pinfunction "IO_L13N_8_AB5") (pintype "bidirectional"))
    )
    (net (code "181") (name "/EXTEND_A42") (class "Default")
      (node (ref "U1") (pin "AB6") (pinfunction "IO_L24N_CC_LC_8_AB6") (pintype "bidirectional"))
    )
    (net (code "182") (name "/EXTEND_A43") (class "Default")
      (node (ref "U1") (pin "AB7") (pinfunction "IO_L28N_VREF_8_AB7") (pintype "bidirectional"))
    )
    (net (code "183") (name "/EXTEND_A44") (class "Default")
      (node (ref "U1") (pin "C2") (pinfunction "IO_L20P_6_C2") (pintype "bidirectional"))
    )
    (net (code "184") (name "/EXTEND_A45") (class "Default")
      (node (ref "U1") (pin "F3") (pinfunction "IO_L27N_6_F3") (pintype "bidirectional"))
    )
    (net (code "185") (name "/EXTEND_A46") (class "Default")
      (node (ref "U1") (pin "H6") (pinfunction "IO_L29P_6_H6") (pintype "bidirectional"))
    )
    (net (code "186") (name "/EXTEND_A47") (class "Default")
      (node (ref "U1") (pin "J6") (pinfunction "IO_L1N_10_J6") (pintype "bidirectional"))
    )
    (net (code "187") (name "/EXTEND_A48") (class "Default")
      (node (ref "U1") (pin "K6") (pinfunction "IO_L3N_10_K6") (pintype "bidirectional"))
    )
    (net (code "188") (name "/EXTEND_A49") (class "Default")
      (node (ref "U1") (pin "L6") (pinfunction "IO_L5N_10_L6") (pintype "bidirectional"))
    )
    (net (code "189") (name "/EXTEND_B0") (class "Default")
      (node (ref "U1") (pin "C1") (pinfunction "IO_L20N_VREF_6_C1") (pintype "bidirectional"))
    )
    (net (code "190") (name "/EXTEND_B1") (class "Default")
      (node (ref "U1") (pin "C4") (pinfunction "IO_L16P_6_C4") (pintype "bidirectional"))
    )
    (net (code "191") (name "/EXTEND_B2") (class "Default")
      (node (ref "U1") (pin "D4") (pinfunction "IO_L16N_6_D4") (pintype "bidirectional"))
    )
    (net (code "192") (name "/EXTEND_B3") (class "Default")
      (node (ref "U1") (pin "D3") (pinfunction "IO_L22P_6_D3") (pintype "bidirectional"))
    )
    (net (code "193") (name "/EXTEND_B4") (class "Default")
      (node (ref "U1") (pin "E4") (pinfunction "IO_L22N_6_E4") (pintype "bidirectional"))
    )
    (net (code "194") (name "/EXTEND_B5") (class "Default")
      (node (ref "U1") (pin "E3") (pinfunction "IO_L24P_CC_LC_6_E3") (pintype "bidirectional"))
    )
    (net (code "195") (name "/EXTEND_B6") (class "Default")
      (node (ref "U1") (pin "F4") (pinfunction "IO_L27P_6_F4") (pintype "bidirectional"))
    )
    (net (code "196") (name "/EXTEND_B7") (class "Default")
      (node (ref "U1") (pin "G4") (pinfunction "IO_L28P_6_G4") (pintype "bidirectional"))
    )
    (net (code "197") (name "/EXTEND_B8") (class "Default")
      (node (ref "U1") (pin "G3") (pinfunction "IO_L28N_VREF_6_G3") (pintype "bidirectional"))
    )
    (net (code "198") (name "/EXTEND_B9") (class "Default")
      (node (ref "U1") (pin "H4") (pinfunction "IO_L31P_6_H4") (pintype "bidirectional"))
    )
    (net (code "199") (name "/EXTEND_B10") (class "Default")
      (node (ref "U1") (pin "H3") (pinfunction "IO_L31N_6_H3") (pintype "bidirectional"))
    )
    (net (code "200") (name "/EXTEND_B11") (class "Default")
      (node (ref "U1") (pin "J4") (pinfunction "IO_L2N_10_J4") (pintype "bidirectional"))
    )
    (net (code "201") (name "/EXTEND_B12") (class "Default")
      (node (ref "U1") (pin "K3") (pinfunction "IO_L7P_10_K3") (pintype "bidirectional"))
    )
    (net (code "202") (name "/EXTEND_B13") (class "Default")
      (node (ref "U1") (pin "K4") (pinfunction "IO_L6N_10_K4") (pintype "bidirectional"))
    )
    (net (code "203") (name "/EXTEND_B14") (class "Default")
      (node (ref "U1") (pin "L4") (pinfunction "IO_L8P_CC_LC_10_L4") (pintype "bidirectional"))
    )
    (net (code "204") (name "/EXTEND_B15") (class "Default")
      (node (ref "U1") (pin "M3") (pinfunction "IO_L12N_VREF_10_M3") (pintype "bidirectional"))
    )
    (net (code "205") (name "/EXTEND_B16") (class "Default")
      (node (ref "U1") (pin "M4") (pinfunction "IO_L12P_10_M4") (pintype "bidirectional"))
    )
    (net (code "206") (name "/EXTEND_B17") (class "Default")
      (node (ref "U1") (pin "N3") (pinfunction "IO_L14P_10_N3") (pintype "bidirectional"))
    )
    (net (code "207") (name "/EXTEND_B18") (class "Default")
      (node (ref "U1") (pin "N4") (pinfunction "IO_L15N_10_N4") (pintype "bidirectional"))
    )
    (net (code "208") (name "/EXTEND_B19") (class "Default")
      (node (ref "U1") (pin "P4") (pinfunction "IO_L18N_10_P4") (pintype "bidirectional"))
    )
    (net (code "209") (name "/EXTEND_B20") (class "Default")
      (node (ref "U1") (pin "P3") (pinfunction "IO_L16P_10_P3") (pintype "bidirectional"))
    )
    (net (code "210") (name "/EXTEND_B21") (class "Default")
      (node (ref "U1") (pin "R4") (pinfunction "IO_L20P_10_R4") (pintype "bidirectional"))
    )
    (net (code "211") (name "/EXTEND_B22") (class "Default")
      (node (ref "U1") (pin "R3") (pinfunction "IO_L20N_VREF_10_R3") (pintype "bidirectional"))
    )
    (net (code "212") (name "/EXTEND_B23") (class "Default")
      (node (ref "U1") (pin "T4") (pinfunction "IO_L26P_10_T4") (pintype "bidirectional"))
    )
    (net (code "213") (name "/EXTEND_B24") (class "Default")
      (node (ref "U1") (pin "U4") (pinfunction "IO_L29N_10_U4") (pintype "bidirectional"))
    )
    (net (code "214") (name "/EXTEND_B25") (class "Default")
      (node (ref "U1") (pin "U3") (pinfunction "IO_L28P_10_U3") (pintype "bidirectional"))
    )
    (net (code "215") (name "/EXTEND_B26") (class "Default")
      (node (ref "U1") (pin "V4") (pinfunction "IO_L29P_10_V4") (pintype "bidirectional"))
    )
    (net (code "216") (name "/EXTEND_B27") (class "Default")
      (node (ref "U1") (pin "W3") (pinfunction "IO_L4N_VREF_8_W3") (pintype "bidirectional"))
    )
    (net (code "217") (name "/EXTEND_B28") (class "Default")
      (node (ref "U1") (pin "W4") (pinfunction "IO_L4P_8_W4") (pintype "bidirectional"))
    )
    (net (code "218") (name "/EXTEND_B29") (class "Default")
      (node (ref "U1") (pin "U2") (pinfunction "IO_L28N_VREF_10_U2") (pintype "bidirectional"))
    )
    (net (code "219") (name "/EXTEND_B30") (class "Default")
      (node (ref "U1") (pin "V2") (pinfunction "IO_L30P_10_V2") (pintype "bidirectional"))
    )
    (net (code "220") (name "/EXTEND_B31") (class "Default")
      (node (ref "U1") (pin "W1") (pinfunction "IO_L1N_8_W1") (pintype "bidirectional"))
    )
    (net (code "221") (name "/EXTEND_B32") (class "Default")
      (node (ref "U1") (pin "W2") (pinfunction "IO_L1P_8_W2") (pintype "bidirectional"))
    )
    (net (code "222") (name "/EXTEND_B33") (class "Default")
      (node (ref "U1") (pin "Y1") (pinfunction "IO_L6N_8_Y1") (pintype "bidirectional"))
    )
    (net (code "223") (name "/EXTEND_B34") (class "Default")
      (node (ref "U1") (pin "Y2") (pinfunction "IO_L6P_8_Y2") (pintype "bidirectional"))
    )
    (net (code "224") (name "/EXTEND_B35") (class "Default")
      (node (ref "U1") (pin "AA1") (pinfunction "IO_L10N_8_AA1") (pintype "bidirectional"))
    )
    (net (code "225") (name "/EXTEND_B36") (class "Default")
      (node (ref "U1") (pin "AB1") (pinfunction "IO_L10P_8_AB1") (pintype "bidirectional"))
    )
    (net (code "226") (name "/EXTEND_B37") (class "Default")
      (node (ref "U1") (pin "AB2") (pinfunction "IO_L12N_VREF_8_AB2") (pintype "bidirectional"))
    )
    (net (code "227") (name "/EXTEND_B38") (class "Default")
      (node (ref "U1") (pin "AC1") (pinfunction "IO_L14N_8_AC1") (pintype "bidirectional"))
    )
    (net (code "228") (name "/EXTEND_B39") (class "Default")
      (node (ref "U1") (pin "AC2") (pinfunction "IO_L14P_8_AC2") (pintype "bidirectional"))
    )
    (net (code "229") (name "/EXTEND_B40") (class "Default")
      (node (ref "U1") (pin "AD1") (pinfunction "IO_L16N_8_AD1") (pintype "bidirectional"))
    )
    (net (code "230") (name "/EXTEND_B41") (class "Default")
      (node (ref "U1") (pin "AD2") (pinfunction "IO_L16P_8_AD2") (pintype "bidirectional"))
    )
    (net (code "231") (name "/EXTEND_B42") (class "Default")
      (node (ref "U1") (pin "Y4") (pinfunction "IO_L8P_CC_LC_8_Y4") (pintype "bidirectional"))
    )
    (net (code "232") (name "/EXTEND_B43") (class "Default")
      (node (ref "U1") (pin "M6") (pinfunction "IO_L13P_10_M6") (pintype "bidirectional"))
    )
    (net (code "233") (name "/EXTEND_B44") (class "Default")
      (node (ref "U1") (pin "P6") (pinfunction "IO_L21N_10_P6") (pintype "bidirectional"))
    )
    (net (code "234") (name "/EXTEND_B45") (class "Default")
      (node (ref "U1") (pin "T6") (pinfunction "IO_L27N_10_T6") (pintype "bidirectional"))
    )
    (net (code "235") (name "/EXTEND_B46") (class "Default")
      (node (ref "U1") (pin "U6") (pinfunction "IO_L32P_10_U6") (pintype "bidirectional"))
    )
    (net (code "236") (name "/EXTEND_B47") (class "Default")
      (node (ref "U1") (pin "V6") (pinfunction "IO_L2P_8_V6") (pintype "bidirectional"))
    )
    (net (code "237") (name "/EXTEND_B48") (class "Default")
      (node (ref "U1") (pin "W6") (pinfunction "IO_L5P_8_W6") (pintype "bidirectional"))
    )
    (net (code "238") (name "/EXTEND_B49") (class "Default")
      (node (ref "U1") (pin "Y6") (pinfunction "IO_L9P_CC_LC_8_Y6") (pintype "bidirectional"))
    )
    (net (code "239") (name "/EXTEND_C0") (class "Default")
      (node (ref "U1") (pin "N20") (pinfunction "IO_L17N_9_N20") (pintype "bidirectional"))
    )
    (net (code "240") (name "/EXTEND_C1") (class "Default")
      (node (ref "U1") (pin "M20") (pinfunction "IO_L13N_9_M20") (pintype "bidirectional"))
    )
    (net (code "241") (name "/EXTEND_C2") (class "Default")
      (node (ref "U1") (pin "L20") (pinfunction "IO_L6N_9_L20") (pintype "bidirectional"))
    )
    (net (code "242") (name "/EXTEND_C3") (class "Default")
      (node (ref "U1") (pin "K20") (pinfunction "IO_L5N_9_K20") (pintype "bidirectional"))
    )
    (net (code "243") (name "/EXTEND_C4") (class "Default")
      (node (ref "U1") (pin "N21") (pinfunction "IO_L17P_9_N21") (pintype "bidirectional"))
    )
    (net (code "244") (name "/EXTEND_C5") (class "Default")
      (node (ref "U1") (pin "M21") (pinfunction "IO_L13P_9_M21") (pintype "bidirectional"))
    )
    (net (code "245") (name "/EXTEND_C6") (class "Default")
      (node (ref "U1") (pin "L21") (pinfunction "IO_L6P_9_L21") (pintype "bidirectional"))
    )
    (net (code "246") (name "/EXTEND_C7") (class "Default")
      (node (ref "U1") (pin "K21") (pinfunction "IO_L3N_9_K21") (pintype "bidirectional"))
    )
    (net (code "247") (name "/EXTEND_C8") (class "Default")
      (node (ref "U1") (pin "J21") (pinfunction "IO_L1P_9_J21") (pintype "bidirectional"))
    )
    (net (code "248") (name "/EXTEND_C9") (class "Default")
      (node (ref "U1") (pin "H21") (pinfunction "IO_L26N_5_H21") (pintype "bidirectional"))
    )
    (net (code "249") (name "/EXTEND_C10") (class "Default")
      (node (ref "U1") (pin "J20") (pinfunction "IO_L1N_9_J20") (pintype "bidirectional"))
    )
    (net (code "250") (name "/EXTEND_C11") (class "Default")
      (node (ref "U1") (pin "H20") (pinfunction "IO_L22P_5_H20") (pintype "bidirectional"))
    )
    (net (code "251") (name "/EXTEND_C12") (class "Default")
      (node (ref "U1") (pin "C26") (pinfunction "IO_L20P_5_C26") (pintype "bidirectional"))
    )
    (net (code "252") (name "/EXTEND_C13") (class "Default")
      (node (ref "U1") (pin "C25") (pinfunction "IO_L20N_VREF_5_C25") (pintype "bidirectional"))
    )
    (net (code "253") (name "/EXTEND_C14") (class "Default")
      (node (ref "U1") (pin "D24") (pinfunction "IO_L16P_5_D24") (pintype "bidirectional"))
    )
    (net (code "254") (name "/EXTEND_C15") (class "Default")
      (node (ref "U1") (pin "B23") (pinfunction "IO_L10N_5_B23") (pintype "bidirectional"))
    )
    (net (code "255") (name "/EXTEND_C16") (class "Default")
      (node (ref "U1") (pin "C24") (pinfunction "IO_L16N_5_C24") (pintype "bidirectional"))
    )
    (net (code "256") (name "/EXTEND_C17") (class "Default")
      (node (ref "U1") (pin "C23") (pinfunction "IO_L21N_5_C23") (pintype "bidirectional"))
    )
    (net (code "257") (name "/EXTEND_C18") (class "Default")
      (node (ref "U1") (pin "D22") (pinfunction "IO_L14P_5_D22") (pintype "bidirectional"))
    )
    (net (code "258") (name "/EXTEND_C19") (class "Default")
      (node (ref "U1") (pin "C22") (pinfunction "IO_L14N_5_C22") (pintype "bidirectional"))
    )
    (net (code "259") (name "/EXTEND_C20") (class "Default")
      (node (ref "U1") (pin "D21") (pinfunction "IO_L12N_VREF_5_D21") (pintype "bidirectional"))
    )
    (net (code "260") (name "/EXTEND_C21") (class "Default")
      (node (ref "U1") (pin "C21") (pinfunction "IO_L6P_5_C21") (pintype "bidirectional"))
    )
    (net (code "261") (name "/EXTEND_C22") (class "Default")
      (node (ref "U1") (pin "D20") (pinfunction "IO_L4P_5_D20") (pintype "bidirectional"))
    )
    (net (code "262") (name "/EXTEND_C23") (class "Default")
      (node (ref "U1") (pin "D19") (pinfunction "IO_L4N_VREF_5_D19") (pintype "bidirectional"))
    )
    (net (code "263") (name "/EXTEND_C24") (class "Default")
      (node (ref "U1") (pin "C19") (pinfunction "IO_L7P_5_C19") (pintype "bidirectional"))
    )
    (net (code "264") (name "/EXTEND_C25") (class "Default")
      (node (ref "U1") (pin "D18") (pinfunction "IO_L7N_5_D18") (pintype "bidirectional"))
    )
    (net (code "265") (name "/EXTEND_C26") (class "Default")
      (node (ref "U1") (pin "C17") (pinfunction "IO_L1P_5_C17") (pintype "bidirectional"))
    )
    (net (code "266") (name "/EXTEND_C27") (class "Default")
      (node (ref "U1") (pin "D17") (pinfunction "IO_L1N_5_D17") (pintype "bidirectional"))
    )
    (net (code "267") (name "/EXTEND_C28") (class "Default")
      (node (ref "U1") (pin "D16") (pinfunction "IO_L7P_D19_LC_1_D16") (pintype "bidirectional"))
    )
    (net (code "268") (name "/EXTEND_C29") (class "Default")
      (node (ref "U1") (pin "C14") (pinfunction "IO_L3N_GC_LC_3_C14") (pintype "bidirectional"))
    )
    (net (code "269") (name "/EXTEND_C30") (class "Default")
      (node (ref "U1") (pin "D15") (pinfunction "IO_L5P_D23_LC_1_D15") (pintype "bidirectional"))
    )
    (net (code "270") (name "/EXTEND_C31") (class "Default")
      (node (ref "U1") (pin "D13") (pinfunction "IO_L4N_D24_VREF_LC_1_D13") (pintype "bidirectional"))
    )
    (net (code "271") (name "/EXTEND_C32") (class "Default")
      (node (ref "U1") (pin "C13") (pinfunction "IO_L8P_GC_LC_3_C13") (pintype "bidirectional"))
    )
    (net (code "272") (name "/EXTEND_C33") (class "Default")
      (node (ref "U1") (pin "C12") (pinfunction "IO_L8N_GC_LC_3_C12") (pintype "bidirectional"))
    )
    (net (code "273") (name "/EXTEND_C34") (class "Default")
      (node (ref "U1") (pin "D11") (pinfunction "IO_L6N_D20_LC_1_D11") (pintype "bidirectional"))
    )
    (net (code "274") (name "/EXTEND_C35") (class "Default")
      (node (ref "U1") (pin "D10") (pinfunction "IO_L1P_6_D10") (pintype "bidirectional"))
    )
    (net (code "275") (name "/EXTEND_C36") (class "Default")
      (node (ref "U1") (pin "C10") (pinfunction "IO_L1N_6_C10") (pintype "bidirectional"))
    )
    (net (code "276") (name "/EXTEND_C37") (class "Default")
      (node (ref "U1") (pin "D9") (pinfunction "IO_L2P_6_D9") (pintype "bidirectional"))
    )
    (net (code "277") (name "/EXTEND_C38") (class "Default")
      (node (ref "U1") (pin "C8") (pinfunction "IO_L2N_6_C8") (pintype "bidirectional"))
    )
    (net (code "278") (name "/EXTEND_C39") (class "Default")
      (node (ref "U1") (pin "D8") (pinfunction "IO_L4P_6_D8") (pintype "bidirectional"))
    )
    (net (code "279") (name "/EXTEND_C40") (class "Default")
      (node (ref "U1") (pin "B10") (pinfunction "IO_L6N_GC_LC_3_B10") (pintype "bidirectional"))
    )
    (net (code "280") (name "/EXTEND_C41") (class "Default")
      (node (ref "U1") (pin "C7") (pinfunction "IO_L11N_6_C7") (pintype "bidirectional"))
    )
    (net (code "281") (name "/EXTEND_C42") (class "Default")
      (node (ref "U1") (pin "A9") (pinfunction "IO_L13P_6_A9") (pintype "bidirectional"))
    )
    (net (code "282") (name "/EXTEND_C43") (class "Default")
      (node (ref "U1") (pin "D7") (pinfunction "IO_L4N_VREF_6_D7") (pintype "bidirectional"))
    )
    (net (code "283") (name "/EXTEND_C44") (class "Default")
      (node (ref "U1") (pin "B9") (pinfunction "IO_L13N_6_B9") (pintype "bidirectional"))
    )
    (net (code "284") (name "/EXTEND_C45") (class "Default")
      (node (ref "U1") (pin "C6") (pinfunction "IO_L8N_CC_LC_6_C6") (pintype "bidirectional"))
    )
    (net (code "285") (name "/EXTEND_C46") (class "Default")
      (node (ref "U1") (pin "A8") (pinfunction "IO_L3P_6_A8") (pintype "bidirectional"))
    )
    (net (code "286") (name "/EXTEND_C47") (class "Default")
      (node (ref "U1") (pin "D6") (pinfunction "IO_L17N_6_D6") (pintype "bidirectional"))
    )
    (net (code "287") (name "/EXTEND_C48") (class "Default")
      (node (ref "U1") (pin "A7") (pinfunction "IO_L3N_6_A7") (pintype "bidirectional"))
    )
    (net (code "288") (name "/EXTEND_C49") (class "Default")
      (node (ref "U1") (pin "B7") (pinfunction "IO_L11P_6_B7") (pintype "bidirectional"))
    )
    (net (code "292") (name "/FPGA_CCLK") (class "Default")
      (node (ref "R20") (pin "1") (pinfunction "1_1") (pintype "passive"))
    )
    (net (code "293") (name "/FPGA_CLK") (class "Default")
      (node (ref "U1") (pin "AE14") (pinfunction "IO_L5P_GC_LC_4_AE14") (pintype "bidirectional"))
    )
    (net (code "294") (name "/FPGA_CLK1") (class "Default")
      (node (ref "U1") (pin "C15") (pinfunction "IO_L3P_GC_LC_3_C15") (pintype "bidirectional"))
    )
    (net (code "296") (name "/FPGA_DONE") (class "Default")
      (node (ref "NT6") (pin "2") (pinfunction "Net2_2") (pintype "passive"))
      (node (ref "R22") (pin "1") (pinfunction "1_1") (pintype "passive"))
      (node (ref "R4") (pin "1") (pinfunction "1_1") (pintype "passive"))
    )
    (net (code "297") (name "/FPGA_ID0") (class "Default")
      (node (ref "NT2") (pin "1") (pinfunction "Net1_1") (pintype "passive"))
    )
    (net (code "298") (name "/FPGA_ID1") (class "Default")
      (node (ref "NT3") (pin "1") (pinfunction "Net1_1") (pintype "passive"))
    )
    (net (code "299") (name "/FPGA_ID2") (class "Default")
      (node (ref "NT4") (pin "1") (pinfunction "Net1_1") (pintype "passive"))
    )
    (net (code "300") (name "/FPGA_ID3") (class "Default")
      (node (ref "NT5") (pin "1") (pinfunction "Net1_1") (pintype "passive"))
    )
    (net (code "301") (name "/FPGA_INIT") (class "Default")
      (node (ref "R3") (pin "1") (pinfunction "1_1") (pintype "passive"))
    )
    (net (code "302") (name "/FPGA_M0") (class "Default")
      (node (ref "R23") (pin "1") (pinfunction "1_1") (pintype "passive"))
    )
    (net (code "303") (name "/FPGA_M1") (class "Default")
      (node (ref "R18") (pin "1") (pinfunction "1_1") (pintype "passive"))
    )
    (net (code "304") (name "/FPGA_M2") (class "Default")
      (node (ref "R14") (pin "1") (pinfunction "1_1") (pintype "passive"))
    )
    (net (code "306") (name "/FPGA_PROGRAM") (class "Default")
      (node (ref "R1") (pin "1") (pinfunction "1_1") (pintype "passive"))
      (node (ref "R24") (pin "1") (pinfunction "1_1") (pintype "passive"))
    )
    (net (code "308") (name "/FPGA_PROG_PWR_ON") (class "Default")
      (node (ref "R7") (pin "1") (pinfunction "1_1") (pintype "passive"))
    )
    (net (code "309") (name "/FPGA_TCK") (class "Default")
      (node (ref "R9") (pin "1") (pinfunction "1_1") (pintype "passive"))
    )
    (net (code "310") (name "/FPGA_TDI") (class "Default")
      (node (ref "R12") (pin "1") (pinfunction "1_1") (pintype "passive"))
    )
    (net (code "311") (name "/FPGA_TDO") (class "Default")
      (node (ref "R10") (pin "1") (pinfunction "1_1") (pintype "passive"))
      (node (ref "R2") (pin "1") (pinfunction "1_1") (pintype "passive"))
    )
    (net (code "312") (name "/FPGA_TMS") (class "Default")
      (node (ref "R8") (pin "1") (pinfunction "1_1") (pintype "passive"))
    )
    (net (code "313") (name "/HSWAP_EN") (class "Default")
      (node (ref "R7") (pin "2") (pinfunction "2_2") (pintype "passive"))
    )
    (net (code "314") (name "/IO0") (class "Default")
      (node (ref "U1") (pin "AE3") (pinfunction "IO_L15N_8_AE3") (pintype "bidirectional"))
    )
    (net (code "315") (name "/IO1") (class "Default")
      (node (ref "U1") (pin "AF3") (pinfunction "IO_L15P_8_AF3") (pintype "bidirectional"))
    )
    (net (code "316") (name "/IO2") (class "Default")
      (node (ref "U1") (pin "AE4") (pinfunction "IO_L17N_8_AE4") (pintype "bidirectional"))
    )
    (net (code "317") (name "/IO3") (class "Default")
      (node (ref "U1") (pin "AF4") (pinfunction "IO_L17P_8_AF4") (pintype "bidirectional"))
    )
    (net (code "318") (name "/IO4") (class "Default")
      (node (ref "U1") (pin "AA4") (pinfunction "IO_L7P_8_AA4") (pintype "bidirectional"))
    )
    (net (code "319") (name "/IO5") (class "Default")
      (node (ref "U1") (pin "AF5") (pinfunction "IO_L19N_8_AF5") (pintype "bidirectional"))
    )
    (net (code "320") (name "/IO6") (class "Default")
      (node (ref "U1") (pin "AB3") (pinfunction "IO_L12P_8_AB3") (pintype "bidirectional"))
    )
    (net (code "321") (name "/IO7") (class "Default")
      (node (ref "U1") (pin "AB4") (pinfunction "IO_L11N_8_AB4") (pintype "bidirectional"))
    )
    (net (code "322") (name "/IO8") (class "Default")
      (node (ref "U1") (pin "AE6") (pinfunction "IO_L30P_8_AE6") (pintype "bidirectional"))
    )
    (net (code "323") (name "/IO9") (class "Default")
      (node (ref "U1") (pin "AF6") (pinfunction "IO_L19P_8_AF6") (pintype "bidirectional"))
    )
    (net (code "324") (name "/IO10") (class "Default")
      (node (ref "U1") (pin "AF7") (pinfunction "IO_L25N_CC_LC_8_AF7") (pintype "bidirectional"))
    )
    (net (code "325") (name "/IO11") (class "Default")
      (node (ref "U1") (pin "AF8") (pinfunction "IO_L25P_CC_LC_8_AF8") (pintype "bidirectional"))
    )
    (net (code "326") (name "/IO12") (class "Default")
      (node (ref "U1") (pin "AE9") (pinfunction "IO_L31N_8_AE9") (pintype "bidirectional"))
    )
    (net (code "327") (name "/IO13") (class "Default")
      (node (ref "U1") (pin "AF9") (pinfunction "IO_L31P_8_AF9") (pintype "bidirectional"))
    )
    (net (code "328") (name "/IO14") (class "Default")
      (node (ref "U1") (pin "AE13") (pinfunction "IO_L5N_GC_LC_4_AE13") (pintype "bidirectional"))
    )
    (net (code "329") (name "/IO15") (class "Default")
      (node (ref "U1") (pin "AF10") (pinfunction "IO_L4N_GC_VREF_LC_4_AF10") (pintype "bidirectional"))
    )
    (net (code "330") (name "/IO16") (class "Default")
      (node (ref "U1") (pin "AF11") (pinfunction "IO_L4P_GC_LC_4_AF11") (pintype "bidirectional"))
    )
    (net (code "331") (name "/IO17") (class "Default")
      (node (ref "U1") (pin "AE12") (pinfunction "IO_L1N_GC_LC_4_AE12") (pintype "bidirectional"))
    )
    (net (code "332") (name "/IO18") (class "Default")
      (node (ref "U1") (pin "AC3") (pinfunction "IO_L18N_8_AC3") (pintype "bidirectional"))
    )
    (net (code "333") (name "/IO19") (class "Default")
      (node (ref "U1") (pin "AC4") (pinfunction "IO_L11P_8_AC4") (pintype "bidirectional"))
    )
    (net (code "334") (name "/IO20") (class "Default")
      (node (ref "U1") (pin "AD3") (pinfunction "IO_L18P_8_AD3") (pintype "bidirectional"))
    )
    (net (code "335") (name "/IO21") (class "Default")
      (node (ref "U1") (pin "AD4") (pinfunction "IO_L22N_8_AD4") (pintype "bidirectional"))
    )
    (net (code "336") (name "/IO22") (class "Default")
      (node (ref "U1") (pin "AC5") (pinfunction "IO_L13P_8_AC5") (pintype "bidirectional"))
    )
    (net (code "337") (name "/IO23") (class "Default")
      (node (ref "U1") (pin "AD5") (pinfunction "IO_L22P_8_AD5") (pintype "bidirectional"))
    )
    (net (code "338") (name "/IO24") (class "Default")
      (node (ref "U1") (pin "M24") (pinfunction "IO_L11N_9_M24") (pintype "bidirectional"))
    )
    (net (code "339") (name "/IO25") (class "Default")
      (node (ref "U1") (pin "N23") (pinfunction "IO_L16P_9_N23") (pintype "bidirectional"))
    )
    (net (code "340") (name "/IO26") (class "Default")
      (node (ref "U1") (pin "AB9") (pinfunction "IO_L29N_8_AB9") (pintype "bidirectional"))
    )
    (net (code "341") (name "/IO27") (class "Default")
      (node (ref "U1") (pin "AB10") (pinfunction "IO_L2N_GC_LC_4_AB10") (pintype "bidirectional"))
    )
    (net (code "342") (name "/IO28") (class "Default")
      (node (ref "U1") (pin "AB13") (pinfunction "IO_L4P_D9_LC_2_AB13") (pintype "bidirectional"))
    )
    (net (code "343") (name "/IO29") (class "Default")
      (node (ref "U1") (pin "AB14") (pinfunction "IO_L1N_D14_CC_LC_2_AB14") (pintype "bidirectional"))
    )
    (net (code "344") (name "/IO30") (class "Default")
      (node (ref "U1") (pin "AC17") (pinfunction "IO_L3N_GC_LC_4_AC17") (pintype "bidirectional"))
    )
    (net (code "345") (name "/IO31") (class "Default")
      (node (ref "U1") (pin "AB17") (pinfunction "IO_L3P_GC_LC_4_AB17") (pintype "bidirectional"))
    )
    (net (code "346") (name "/IO32") (class "Default")
      (node (ref "U1") (pin "AB18") (pinfunction "IO_L29N_SM4_7_AB18") (pintype "bidirectional"))
    )
    (net (code "347") (name "/IO33") (class "Default")
      (node (ref "U1") (pin "W19") (pinfunction "IO_L18N_7_W19") (pintype "bidirectional"))
    )
    (net (code "348") (name "/IO34") (class "Default")
      (node (ref "U1") (pin "AB20") (pinfunction "IO_L28P_7_AB20") (pintype "bidirectional"))
    )
    (net (code "349") (name "/IO35") (class "Default")
      (node (ref "U1") (pin "AB21") (pinfunction "IO_L24N_CC_LC_7_AB21") (pintype "bidirectional"))
    )
    (net (code "350") (name "/KBCLOCK") (class "Default")
      (node (ref "U1") (pin "A17") (pinfunction "IO_L7N_GC_LC_3_A17") (pintype "bidirectional"))
    )
    (net (code "351") (name "/KBDATA") (class "Default")
      (node (ref "U1") (pin "B17") (pinfunction "IO_L7P_GC_LC_3_B17") (pintype "bidirectional"))
    )
    (net (code "352") (name "/LED0") (class "Default")
      (node (ref "U1") (pin "AD6") (pinfunction "IO_L30N_8_AD6") (pintype "bidirectional"))
    )
    (net (code "353") (name "/LED1") (class "Default")
      (node (ref "U1") (pin "AC7") (pinfunction "IO_L28P_8_AC7") (pintype "bidirectional"))
    )
    (net (code "354") (name "/LED2") (class "Default")
      (node (ref "U1") (pin "AC8") (pinfunction "IO_L32N_8_AC8") (pintype "bidirectional"))
    )
    (net (code "355") (name "/LED3") (class "Default")
      (node (ref "U1") (pin "AD8") (pinfunction "IO_L32P_8_AD8") (pintype "bidirectional"))
    )
    (net (code "356") (name "/LED4") (class "Default")
      (node (ref "U1") (pin "AC9") (pinfunction "IO_L29P_8_AC9") (pintype "bidirectional"))
    )
    (net (code "357") (name "/LED5") (class "Default")
      (node (ref "U1") (pin "AD10") (pinfunction "IO_L6N_GC_LC_4_AD10") (pintype "bidirectional"))
    )
    (net (code "358") (name "/LED6") (class "Default")
      (node (ref "U1") (pin "AC10") (pinfunction "IO_L2P_GC_LC_4_AC10") (pintype "bidirectional"))
    )
    (net (code "359") (name "/LED7") (class "Default")
      (node (ref "U1") (pin "AC11") (pinfunction "IO_L2N_D12_LC_2_AC11") (pintype "bidirectional"))
    )
    (net (code "360") (name "/M0") (class "Default")
      (node (ref "R23") (pin "2") (pinfunction "2_2") (pintype "passive"))
    )
    (net (code "361") (name "/M1") (class "Default")
      (node (ref "R18") (pin "2") (pinfunction "2_2") (pintype "passive"))
    )
    (net (code "362") (name "/M2") (class "Default")
      (node (ref "R14") (pin "2") (pinfunction "2_2") (pintype "passive"))
    )
    (net (code "364") (name "/MOUSECLOCK") (class "Default")
      (node (ref "U1") (pin "A18") (pinfunction "IO_L3N_5_A18") (pintype "bidirectional"))
    )
    (net (code "365") (name "/MOUSEDATA") (class "Default")
      (node (ref "U1") (pin "B18") (pinfunction "IO_L3P_5_B18") (pintype "bidirectional"))
    )
    (net (code "366") (name "/NEXUS_TCK") (class "Default")
      (node (ref "U1") (pin "A12") (pinfunction "IO_L2P_GC_VRN_LC_3_A12") (pintype "bidirectional"))
    )
    (net (code "367") (name "/NEXUS_TDI") (class "Default")
      (node (ref "U1") (pin "U21") (pinfunction "IO_L29N_9_U21") (pintype "bidirectional"))
    )
    (net (code "368") (name "/NEXUS_TDO") (class "Default")
      (node (ref "U1") (pin "B24") (pinfunction "IO_L10P_5_B24") (pintype "bidirectional"))
    )
    (net (code "369") (name "/NEXUS_TMS") (class "Default")
      (node (ref "U1") (pin "T24") (pinfunction "IO_L24P_CC_LC_9_T24") (pintype "bidirectional"))
    )
    (net (code "371") (name "/ONE_WIRE_DB_PB") (class "Default")
      (node (ref "U1") (pin "AA8") (pinfunction "IO_L26P_8_AA8") (pintype "bidirectional"))
    )
    (net (code "376") (name "/PROG_B") (class "Default")
      (node (ref "R24") (pin "2") (pinfunction "2_2") (pintype "passive"))
    )
    (net (code "377") (name "/REF_CLK") (class "Default")
      (node (ref "U1") (pin "AE10") (pinfunction "IO_L6P_GC_LC_4_AE10") (pintype "bidirectional"))
    )
    (net (code "378") (name "/RS232_CTS") (class "Default")
      (node (ref "U1") (pin "B14") (pinfunction "IO_L1N_GC_CC_LC_3_B14") (pintype "bidirectional"))
    )
    (net (code "379") (name "/RS232_RTS") (class "Default")
      (node (ref "U1") (pin "B13") (pinfunction "IO_L4P_GC_LC_3_B13") (pintype "bidirectional"))
    )
    (net (code "380") (name "/RS232_RX") (class "Default")
      (node (ref "U1") (pin "A16") (pinfunction "IO_L5P_GC_LC_3_A16") (pintype "bidirectional"))
    )
    (net (code "381") (name "/RS232_TX") (class "Default")
      (node (ref "U1") (pin "A15") (pinfunction "IO_L5N_GC_LC_3_A15") (pintype "bidirectional"))
    )
    (net (code "382") (name "/SCL") (class "Default")
      (node (ref "U1") (pin "AA7") (pinfunction "IO_L20P_8_AA7") (pintype "bidirectional"))
    )
    (net (code "383") (name "/SDA") (class "Default")
      (node (ref "U1") (pin "AA3") (pinfunction "IO_L7N_8_AA3") (pintype "bidirectional"))
    )
    (net (code "385") (name "/SPI_CLK") (class "Default")
      (node (ref "U1") (pin "D12") (pinfunction "IO_L8N_D16_CC_LC_1_D12") (pintype "bidirectional"))
    )
    (net (code "386") (name "/SPI_DIN") (class "Default")
      (node (ref "U1") (pin "C11") (pinfunction "IO_L6P_D21_LC_1_C11") (pintype "bidirectional"))
    )
    (net (code "387") (name "/SPI_DOUT") (class "Default")
      (node (ref "U1") (pin "G10") (pinfunction "IO_L9P_CC_LC_6_G10") (pintype "bidirectional"))
    )
    (net (code "388") (name "/SPI_MODE") (class "Default")
      (node (ref "U1") (pin "E14") (pinfunction "IO_L5N_D22_LC_1_E14") (pintype "bidirectional"))
    )
    (net (code "389") (name "/SPI_SEL") (class "Default")
      (node (ref "U1") (pin "E13") (pinfunction "IO_L8P_D17_CC_LC_1_E13") (pintype "bidirectional"))
    )
    (net (code "390") (name "/SRAM1_A0") (class "Default")
      (node (ref "U1") (pin "V22") (pinfunction "IO_L1N_7_V22") (pintype "bidirectional"))
    )
    (net (code "391") (name "/SRAM1_A1") (class "Default")
      (node (ref "U1") (pin "U22") (pinfunction "IO_L29P_9_U22") (pintype "bidirectional"))
    )
    (net (code "392") (name "/SRAM1_A2") (class "Default")
      (node (ref "U1") (pin "P23") (pinfunction "IO_L19P_9_P23") (pintype "bidirectional"))
    )
    (net (code "393") (name "/SRAM1_A3") (class "Default")
      (node (ref "U1") (pin "Y17") (pinfunction "IO_L27P_SM5_7_Y17") (pintype "bidirectional"))
    )
    (net (code "394") (name "/SRAM1_A4") (class "Default")
      (node (ref "U1") (pin "Y18") (pinfunction "IO_L21N_7_Y18") (pintype "bidirectional"))
    )
    (net (code "395") (name "/SRAM1_A5") (class "Default")
      (node (ref "U1") (pin "V20") (pinfunction "IO_L5N_7_V20") (pintype "bidirectional"))
    )
    (net (code "396") (name "/SRAM1_A6") (class "Default")
      (node (ref "U1") (pin "U20") (pinfunction "IO_L31P_9_U20") (pintype "bidirectional"))
    )
    (net (code "397") (name "/SRAM1_A7") (class "Default")
      (node (ref "U1") (pin "T20") (pinfunction "IO_L30N_9_T20") (pintype "bidirectional"))
    )
    (net (code "398") (name "/SRAM1_A8") (class "Default")
      (node (ref "U1") (pin "R20") (pinfunction "IO_L25P_CC_LC_9_R20") (pintype "bidirectional"))
    )
    (net (code "399") (name "/SRAM1_A9") (class "Default")
      (node (ref "U1") (pin "P20") (pinfunction "IO_L21P_9_P20") (pintype "bidirectional"))
    )
    (net (code "400") (name "/SRAM1_A10") (class "Default")
      (node (ref "U1") (pin "V21") (pinfunction "IO_L1P_7_V21") (pintype "bidirectional"))
    )
    (net (code "401") (name "/SRAM1_A11") (class "Default")
      (node (ref "U1") (pin "W21") (pinfunction "IO_L3P_7_W21") (pintype "bidirectional"))
    )
    (net (code "402") (name "/SRAM1_A12") (class "Default")
      (node (ref "U1") (pin "Y21") (pinfunction "IO_L20N_VREF_7_Y21") (pintype "bidirectional"))
    )
    (net (code "403") (name "/SRAM1_A13") (class "Default")
      (node (ref "U1") (pin "AA20") (pinfunction "IO_L26N_SM6_7_AA20") (pintype "bidirectional"))
    )
    (net (code "404") (name "/SRAM1_A14") (class "Default")
      (node (ref "U1") (pin "AA19") (pinfunction "IO_L26P_SM6_7_AA19") (pintype "bidirectional"))
    )
    (net (code "405") (name "/SRAM1_A15") (class "Default")
      (node (ref "U1") (pin "AC21") (pinfunction "IO_L24P_CC_LC_7_AC21") (pintype "bidirectional"))
    )
    (net (code "406") (name "/SRAM1_A16") (class "Default")
      (node (ref "U1") (pin "AD21") (pinfunction "IO_L32N_SM1_7_AD21") (pintype "bidirectional"))
    )
    (net (code "407") (name "/SRAM1_A17") (class "Default")
      (node (ref "U1") (pin "AC20") (pinfunction "IO_L28N_VREF_7_AC20") (pintype "bidirectional"))
    )
    (net (code "408") (name "/SRAM1_A18") (class "Default")
      (node (ref "U1") (pin "AA18") (pinfunction "IO_L21P_7_AA18") (pintype "bidirectional"))
    )
    (net (code "410") (name "/SRAM1_D0") (class "Default")
      (node (ref "U1") (pin "Y20") (pinfunction "IO_L20P_7_Y20") (pintype "bidirectional"))
    )
    (net (code "411") (name "/SRAM1_D1") (class "Default")
      (node (ref "U1") (pin "AD11") (pinfunction "IO_L8N_GC_CC_LC_4_AD11") (pintype "bidirectional"))
    )
    (net (code "412") (name "/SRAM1_D2") (class "Default")
      (node (ref "U1") (pin "T19") (pinfunction "IO_L31N_9_T19") (pintype "bidirectional"))
    )
    (net (code "413") (name "/SRAM1_D3") (class "Default")
      (node (ref "U1") (pin "R19") (pinfunction "IO_L25N_CC_LC_9_R19") (pintype "bidirectional"))
    )
    (net (code "414") (name "/SRAM1_D4") (class "Default")
      (node (ref "U1") (pin "P22") (pinfunction "IO_L19N_9_P22") (pintype "bidirectional"))
    )
    (net (code "415") (name "/SRAM1_D5") (class "Default")
      (node (ref "U1") (pin "P19") (pinfunction "IO_L21N_9_P19") (pintype "bidirectional"))
    )
    (net (code "416") (name "/SRAM1_D6") (class "Default")
      (node (ref "U1") (pin "N19") (pinfunction "IO_L9N_CC_LC_9_N19") (pintype "bidirectional"))
    )
    (net (code "417") (name "/SRAM1_D7") (class "Default")
      (node (ref "U1") (pin "N22") (pinfunction "IO_L16N_9_N22") (pintype "bidirectional"))
    )
    (net (code "418") (name "/SRAM1_D8") (class "Default")
      (node (ref "U1") (pin "AA17") (pinfunction "IO_L27N_SM5_7_AA17") (pintype "bidirectional"))
    )
    (net (code "419") (name "/SRAM1_D9") (class "Default")
      (node (ref "U1") (pin "AA16") (pinfunction "IO_L3P_D11_LC_2_AA16") (pintype "bidirectional"))
    )
    (net (code "420") (name "/SRAM1_D10") (class "Default")
      (node (ref "U1") (pin "AA15") (pinfunction "IO_L3N_D10_LC_2_AA15") (pintype "bidirectional"))
    )
    (net (code "421") (name "/SRAM1_D11") (class "Default")
      (node (ref "U1") (pin "Y23") (pinfunction "IO_L12N_VREF_7_Y23") (pintype "bidirectional"))
    )
    (net (code "422") (name "/SRAM1_D12") (class "Default")
      (node (ref "U1") (pin "AA24") (pinfunction "IO_L8P_CC_LC_7_AA24") (pintype "bidirectional"))
    )
    (net (code "423") (name "/SRAM1_D13") (class "Default")
      (node (ref "U1") (pin "AA23") (pinfunction "IO_L14N_7_AA23") (pintype "bidirectional"))
    )
    (net (code "424") (name "/SRAM1_D14") (class "Default")
      (node (ref "U1") (pin "AB24") (pinfunction "IO_L7P_7_AB24") (pintype "bidirectional"))
    )
    (net (code "425") (name "/SRAM1_D15") (class "Default")
      (node (ref "U1") (pin "AC16") (pinfunction "IO_L7P_D3_LC_2_AC16") (pintype "bidirectional"))
    )
    (net (code "426") (name "/SRAM1_NBHE") (class "Default")
      (node (ref "U1") (pin "AD19") (pinfunction "IO_L25P_CC_SM7_LC_7_AD19") (pintype "bidirectional"))
    )
    (net (code "427") (name "/SRAM1_NBLE") (class "Default")
      (node (ref "U1") (pin "AC18") (pinfunction "IO_L29P_SM4_7_AC18") (pintype "bidirectional"))
    )
    (net (code "428") (name "/SRAM1_NCS") (class "Default")
      (node (ref "U1") (pin "Y19") (pinfunction "IO_L18P_7_Y19") (pintype "bidirectional"))
    )
    (net (code "429") (name "/SRAM1_NOE") (class "Default")
      (node (ref "U1") (pin "AC19") (pinfunction "IO_L25N_CC_SM7_LC_7_AC19") (pintype "bidirectional"))
    )
    (net (code "430") (name "/SRAM1_NWE") (class "Default")
      (node (ref "U1") (pin "W20") (pinfunction "IO_L5P_7_W20") (pintype "bidirectional"))
    )
    (net (code "432") (name "/SRAM2_A0") (class "Default")
      (node (ref "U1") (pin "N25") (pinfunction "IO_L15P_9_N25") (pintype "bidirectional"))
    )
    (net (code "433") (name "/SRAM2_A1") (class "Default")
      (node (ref "U1") (pin "M26") (pinfunction "IO_L12N_VREF_9_M26") (pintype "bidirectional"))
    )
    (net (code "434") (name "/SRAM2_A2") (class "Default")
      (node (ref "U1") (pin "M25") (pinfunction "IO_L11P_9_M25") (pintype "bidirectional"))
    )
    (net (code "435") (name "/SRAM2_A3") (class "Default")
      (node (ref "U1") (pin "L26") (pinfunction "IO_L12P_9_L26") (pintype "bidirectional"))
    )
    (net (code "436") (name "/SRAM2_A4") (class "Default")
      (node (ref "U1") (pin "AD22") (pinfunction "IO_L15P_7_AD22") (pintype "bidirectional"))
    )
    (net (code "437") (name "/SRAM2_A5") (class "Default")
      (node (ref "U1") (pin "U23") (pinfunction "IO_L27P_9_U23") (pintype "bidirectional"))
    )
    (net (code "438") (name "/SRAM2_A6") (class "Default")
      (node (ref "U1") (pin "T23") (pinfunction "IO_L24N_CC_LC_9_T23") (pintype "bidirectional"))
    )
    (net (code "439") (name "/SRAM2_A7") (class "Default")
      (node (ref "U1") (pin "R24") (pinfunction "IO_L22P_9_R24") (pintype "bidirectional"))
    )
    (net (code "440") (name "/SRAM2_A8") (class "Default")
      (node (ref "U1") (pin "R23") (pinfunction "IO_L22N_9_R23") (pintype "bidirectional"))
    )
    (net (code "441") (name "/SRAM2_A9") (class "Default")
      (node (ref "U1") (pin "P24") (pinfunction "IO_L18N_9_P24") (pintype "bidirectional"))
    )
    (net (code "442") (name "/SRAM2_A10") (class "Default")
      (node (ref "U1") (pin "P25") (pinfunction "IO_L18P_9_P25") (pintype "bidirectional"))
    )
    (net (code "443") (name "/SRAM2_A11") (class "Default")
      (node (ref "U1") (pin "R26") (pinfunction "IO_L20P_9_R26") (pintype "bidirectional"))
    )
    (net (code "444") (name "/SRAM2_A12") (class "Default")
      (node (ref "U1") (pin "R25") (pinfunction "IO_L20N_VREF_9_R25") (pintype "bidirectional"))
    )
    (net (code "445") (name "/SRAM2_A13") (class "Default")
      (node (ref "U1") (pin "T26") (pinfunction "IO_L26P_9_T26") (pintype "bidirectional"))
    )
    (net (code "446") (name "/SRAM2_A14") (class "Default")
      (node (ref "U1") (pin "U26") (pinfunction "IO_L26N_9_U26") (pintype "bidirectional"))
    )
    (net (code "447") (name "/SRAM2_A15") (class "Default")
      (node (ref "U1") (pin "AD26") (pinfunction "IO_L11N_7_AD26") (pintype "bidirectional"))
    )
    (net (code "448") (name "/SRAM2_A16") (class "Default")
      (node (ref "U1") (pin "AE24") (pinfunction "IO_L22N_7_AE24") (pintype "bidirectional"))
    )
    (net (code "449") (name "/SRAM2_A17") (class "Default")
      (node (ref "U1") (pin "AF24") (pinfunction "IO_L22P_7_AF24") (pintype "bidirectional"))
    )
    (net (code "450") (name "/SRAM2_A18") (class "Default")
      (node (ref "U1") (pin "U25") (pinfunction "IO_L28P_9_U25") (pintype "bidirectional"))
    )
    (net (code "451") (name "/SRAM2_D0") (class "Default")
      (node (ref "U1") (pin "AD23") (pinfunction "IO_L15N_7_AD23") (pintype "bidirectional"))
    )
    (net (code "452") (name "/SRAM2_D1") (class "Default")
      (node (ref "U1") (pin "AC23") (pinfunction "IO_L16P_7_AC23") (pintype "bidirectional"))
    )
    (net (code "453") (name "/SRAM2_D2") (class "Default")
      (node (ref "U1") (pin "AC24") (pinfunction "IO_L16N_7_AC24") (pintype "bidirectional"))
    )
    (net (code "454") (name "/SRAM2_D3") (class "Default")
      (node (ref "U1") (pin "AB23") (pinfunction "IO_L14P_7_AB23") (pintype "bidirectional"))
    )
    (net (code "455") (name "/SRAM2_D4") (class "Default")
      (node (ref "U1") (pin "Y24") (pinfunction "IO_L8N_CC_LC_7_Y24") (pintype "bidirectional"))
    )
    (net (code "456") (name "/SRAM2_D5") (class "Default")
      (node (ref "U1") (pin "W23") (pinfunction "IO_L4P_7_W23") (pintype "bidirectional"))
    )
    (net (code "457") (name "/SRAM2_D6") (class "Default")
      (node (ref "U1") (pin "W24") (pinfunction "IO_L4N_VREF_7_W24") (pintype "bidirectional"))
    )
    (net (code "458") (name "/SRAM2_D7") (class "Default")
      (node (ref "U1") (pin "V23") (pinfunction "IO_L27N_9_V23") (pintype "bidirectional"))
    )
    (net (code "459") (name "/SRAM2_D8") (class "Default")
      (node (ref "U1") (pin "V26") (pinfunction "IO_L32P_9_V26") (pintype "bidirectional"))
    )
    (net (code "460") (name "/SRAM2_D9") (class "Default")
      (node (ref "U1") (pin "V25") (pinfunction "IO_L32N_9_V25") (pintype "bidirectional"))
    )
    (net (code "461") (name "/SRAM2_D10") (class "Default")
      (node (ref "U1") (pin "W26") (pinfunction "IO_L2N_7_W26") (pintype "bidirectional"))
    )
    (net (code "462") (name "/SRAM2_D11") (class "Default")
      (node (ref "U1") (pin "W25") (pinfunction "IO_L2P_7_W25") (pintype "bidirectional"))
    )
    (net (code "463") (name "/SRAM2_D12") (class "Default")
      (node (ref "U1") (pin "Y26") (pinfunction "IO_L6N_7_Y26") (pintype "bidirectional"))
    )
    (net (code "464") (name "/SRAM2_D13") (class "Default")
      (node (ref "U1") (pin "Y25") (pinfunction "IO_L6P_7_Y25") (pintype "bidirectional"))
    )
    (net (code "465") (name "/SRAM2_D14") (class "Default")
      (node (ref "U1") (pin "AA26") (pinfunction "IO_L10N_7_AA26") (pintype "bidirectional"))
    )
    (net (code "466") (name "/SRAM2_D15") (class "Default")
      (node (ref "U1") (pin "AB26") (pinfunction "IO_L10P_7_AB26") (pintype "bidirectional"))
    )
    (net (code "468") (name "/SRAM2_NBHE") (class "Default")
      (node (ref "U1") (pin "AC26") (pinfunction "IO_L9N_CC_LC_7_AC26") (pintype "bidirectional"))
    )
    (net (code "469") (name "/SRAM2_NBLE") (class "Default")
      (node (ref "U1") (pin "AB25") (pinfunction "IO_L7N_7_AB25") (pintype "bidirectional"))
    )
    (net (code "470") (name "/SRAM2_NCS") (class "Default")
      (node (ref "U1") (pin "AC22") (pinfunction "IO_L13P_7_AC22") (pintype "bidirectional"))
    )
    (net (code "471") (name "/SRAM2_NOE") (class "Default")
      (node (ref "U1") (pin "AC25") (pinfunction "IO_L9P_CC_LC_7_AC25") (pintype "bidirectional"))
    )
    (net (code "472") (name "/SRAM2_NWE") (class "Default")
      (node (ref "U1") (pin "U24") (pinfunction "IO_L28N_VREF_9_U24") (pintype "bidirectional"))
    )
    (net (code "474") (name "/STATUS_LED") (class "Default")
      (node (ref "NT6") (pin "1") (pinfunction "Net1_1") (pintype "passive"))
    )
    (net (code "475") (name "/SW0") (class "Default")
      (node (ref "U1") (pin "AE18") (pinfunction "IO_L31N_SM2_7_AE18") (pintype "bidirectional"))
    )
    (net (code "476") (name "/SW1") (class "Default")
      (node (ref "U1") (pin "AF19") (pinfunction "IO_L17P_7_AF19") (pintype "bidirectional"))
    )
    (net (code "477") (name "/SW2") (class "Default")
      (node (ref "U1") (pin "AF20") (pinfunction "IO_L17N_7_AF20") (pintype "bidirectional"))
    )
    (net (code "478") (name "/SW3") (class "Default")
      (node (ref "U1") (pin "AF21") (pinfunction "IO_L30P_SM3_7_AF21") (pintype "bidirectional"))
    )
    (net (code "479") (name "/SW4") (class "Default")
      (node (ref "U1") (pin "AE21") (pinfunction "IO_L32P_SM1_7_AE21") (pintype "bidirectional"))
    )
    (net (code "481") (name "/TCK") (class "Default")
      (node (ref "R9") (pin "2") (pinfunction "2_2") (pintype "passive"))
    )
    (net (code "482") (name "/TDI") (class "Default")
      (node (ref "R12") (pin "2") (pinfunction "2_2") (pintype "passive"))
    )
    (net (code "483") (name "/TDO") (class "Default")
      (node (ref "R10") (pin "2") (pinfunction "2_2") (pintype "passive"))
    )
    (net (code "485") (name "/TMS") (class "Default")
      (node (ref "R8") (pin "2") (pinfunction "2_2") (pintype "passive"))
    )
    (net (code "486") (name "/UNUSED1") (class "Default")
      (node (ref "U1") (pin "D23") (pinfunction "IO_L21P_5_D23") (pintype "bidirectional"))
    )
    (net (code "487") (name "/UNUSED2") (class "Default")
      (node (ref "U1") (pin "AB22") (pinfunction "IO_L13N_7_AB22") (pintype "bidirectional"))
    )
    (net (code "488") (name "/UNUSED3") (class "Default")
      (node (ref "U1") (pin "Y22") (pinfunction "IO_L12P_7_Y22") (pintype "bidirectional"))
    )
    (net (code "489") (name "/UNUSED4") (class "Default")
      (node (ref "U1") (pin "M8") (pinfunction "IO_L9P_CC_LC_10_M8") (pintype "bidirectional"))
    )
    (net (code "490") (name "/UNUSED5") (class "Default")
      (node (ref "U1") (pin "L8") (pinfunction "IO_L9N_CC_LC_10_L8") (pintype "bidirectional"))
    )
    (net (code "491") (name "/UNUSED6") (class "Default")
      (node (ref "U1") (pin "W22") (pinfunction "IO_L3N_7_W22") (pintype "bidirectional"))
    )
    (net (code "494") (name "/VRN_7") (class "Default")
      (node (ref "U1") (pin "AD17") (pinfunction "IO_L7P_GC_VRN_LC_4_AD17") (pintype "bidirectional"))
    )
    (net (code "495") (name "/VRP_7") (class "Default")
      (node (ref "U1") (pin "AD16") (pinfunction "IO_L7N_GC_VRP_LC_4_AD16") (pintype "bidirectional"))
    )
    (net (code "515") (name "3V3") (class "Default")
      (node (ref "C23_CM") (pin "1") (pinfunction "1_1") (pintype "passive"))
      (node (ref "C24_CM") (pin "1") (pinfunction "1_1") (pintype "passive"))
      (node (ref "R1") (pin "2") (pinfunction "2_2") (pintype "passive"))
      (node (ref "R2") (pin "2") (pinfunction "2_2") (pintype "passive"))
      (node (ref "R3") (pin "2") (pinfunction "2_2") (pintype "passive"))
      (node (ref "R4") (pin "2") (pinfunction "2_2") (pintype "passive"))
    )
    (net (code "516") (name "GND") (class "Default")
      (node (ref "C23_CM") (pin "2") (pinfunction "2_2") (pintype "passive"))
      (node (ref "C24_CM") (pin "2") (pinfunction "2_2") (pintype "passive"))
      (node (ref "NT2") (pin "2") (pinfunction "Net2_2") (pintype "passive"))
      (node (ref "NT3") (pin "2") (pinfunction "Net2_2") (pintype "passive"))
      (node (ref "NT4") (pin "2") (pinfunction "Net2_2") (pintype "passive"))
      (node (ref "NT5") (pin "2") (pinfunction "Net2_2") (pintype "passive"))
    )
    (net (code "517") (name "unconnected-(U1C-IO_L2N_GC_VRP_LC_3-PadA11)") (class "Default")
      (node (ref "U1") (pin "A11") (pinfunction "IO_L2N_GC_VRP_LC_3_A11") (pintype "bidirectional"))
    )
    (net (code "518") (name "unconnected-(U1E-IO_L23N_VRP_5-PadG21)") (class "Default")
      (node (ref "U1") (pin "G21") (pinfunction "IO_L23N_VRP_5_G21") (pintype "bidirectional"))
    )
    (net (code "519") (name "unconnected-(U1E-IO_L23P_VRN_5-PadG22)") (class "Default")
      (node (ref "U1") (pin "G22") (pinfunction "IO_L23P_VRN_5_G22") (pintype "bidirectional"))
    )
    (net (code "520") (name "unconnected-(U1F-IO_L6N_6-PadA5)") (class "Default")
      (node (ref "U1") (pin "A5") (pinfunction "IO_L6N_6_A5") (pintype "bidirectional"))
    )
    (net (code "521") (name "unconnected-(U1F-IO_L7P_6-PadE9)") (class "Default")
      (node (ref "U1") (pin "E9") (pinfunction "IO_L7P_6_E9") (pintype "bidirectional"))
    )
    (net (code "522") (name "unconnected-(U1F-IO_L12N_VREF_6-PadD5)") (class "Default")
      (node (ref "U1") (pin "D5") (pinfunction "IO_L12N_VREF_6_D5") (pintype "bidirectional"))
    )
    (net (code "523") (name "unconnected-(U1F-IO_L12P_6-PadC5)") (class "Default")
      (node (ref "U1") (pin "C5") (pinfunction "IO_L12P_6_C5") (pintype "bidirectional"))
    )
    (net (code "524") (name "unconnected-(U1F-IO_L14N_6-PadB3)") (class "Default")
      (node (ref "U1") (pin "B3") (pinfunction "IO_L14N_6_B3") (pintype "bidirectional"))
    )
    (net (code "525") (name "unconnected-(U1F-IO_L14P_6-PadA3)") (class "Default")
      (node (ref "U1") (pin "A3") (pinfunction "IO_L14P_6_A3") (pintype "bidirectional"))
    )
    (net (code "526") (name "unconnected-(U1F-IO_L15N_6-PadB4)") (class "Default")
      (node (ref "U1") (pin "B4") (pinfunction "IO_L15N_6_B4") (pintype "bidirectional"))
    )
    (net (code "527") (name "unconnected-(U1F-IO_L15P_6-PadA4)") (class "Default")
      (node (ref "U1") (pin "A4") (pinfunction "IO_L15P_6_A4") (pintype "bidirectional"))
    )
    (net (code "528") (name "unconnected-(U1F-IO_L17P_6-PadE7)") (class "Default")
      (node (ref "U1") (pin "E7") (pinfunction "IO_L17P_6_E7") (pintype "bidirectional"))
    )
    (net (code "529") (name "unconnected-(U1F-IO_L21N_6-PadH7)") (class "Default")
      (node (ref "U1") (pin "H7") (pinfunction "IO_L21N_6_H7") (pintype "bidirectional"))
    )
    (net (code "530") (name "unconnected-(U1F-IO_L21P_6-PadH8)") (class "Default")
      (node (ref "U1") (pin "H8") (pinfunction "IO_L21P_6_H8") (pintype "bidirectional"))
    )
    (net (code "531") (name "unconnected-(U1F-IO_L23N_VRP_6-PadG5)") (class "Default")
      (node (ref "U1") (pin "G5") (pinfunction "IO_L23N_VRP_6_G5") (pintype "bidirectional"))
    )
    (net (code "532") (name "unconnected-(U1F-IO_L23P_VRN_6-PadG6)") (class "Default")
      (node (ref "U1") (pin "G6") (pinfunction "IO_L23P_VRN_6_G6") (pintype "bidirectional"))
    )
    (net (code "533") (name "unconnected-(U1G-IO_L11P_7-PadAD25)") (class "Default")
      (node (ref "U1") (pin "AD25") (pinfunction "IO_L11P_7_AD25") (pintype "bidirectional"))
    )
    (net (code "534") (name "unconnected-(U1G-IO_L23N_VRP_7-PadAD20)") (class "Default")
      (node (ref "U1") (pin "AD20") (pinfunction "IO_L23N_VRP_7_AD20") (pintype "bidirectional"))
    )
    (net (code "535") (name "unconnected-(U1G-IO_L23P_VRN_7-PadAE20)") (class "Default")
      (node (ref "U1") (pin "AE20") (pinfunction "IO_L23P_VRN_7_AE20") (pintype "bidirectional"))
    )
    (net (code "536") (name "unconnected-(U1H-IO_L23N_VRP_8-PadAD7)") (class "Default")
      (node (ref "U1") (pin "AD7") (pinfunction "IO_L23N_VRP_8_AD7") (pintype "bidirectional"))
    )
    (net (code "537") (name "unconnected-(U1H-IO_L23P_VRN_8-PadAE7)") (class "Default")
      (node (ref "U1") (pin "AE7") (pinfunction "IO_L23P_VRN_8_AE7") (pintype "bidirectional"))
    )
    (net (code "538") (name "unconnected-(U1I-IO_L15N_9-PadN24)") (class "Default")
      (node (ref "U1") (pin "N24") (pinfunction "IO_L15N_9_N24") (pintype "bidirectional"))
    )
    (net (code "539") (name "unconnected-(U1I-IO_L23N_VRP_9-PadR21)") (class "Default")
      (node (ref "U1") (pin "R21") (pinfunction "IO_L23N_VRP_9_R21") (pintype "bidirectional"))
    )
    (net (code "540") (name "unconnected-(U1I-IO_L23P_VRN_9-PadR22)") (class "Default")
      (node (ref "U1") (pin "R22") (pinfunction "IO_L23P_VRN_9_R22") (pintype "bidirectional"))
    )
    (net (code "541") (name "unconnected-(U1I-IO_L30P_9-PadT21)") (class "Default")
      (node (ref "U1") (pin "T21") (pinfunction "IO_L30P_9_T21") (pintype "bidirectional"))
    )
    (net (code "542") (name "unconnected-(U1J-IO_L23N_VRP_10-PadR5)") (class "Default")
      (node (ref "U1") (pin "R5") (pinfunction "IO_L23N_VRP_10_R5") (pintype "bidirectional"))
    )
    (net (code "543") (name "unconnected-(U1J-IO_L23P_VRN_10-PadR6)") (class "Default")
      (node (ref "U1") (pin "R6") (pinfunction "IO_L23P_VRN_10_R6") (pintype "bidirectional"))
    )
  )
)
